# Controller.net
KiCad netlist of a schematic drawn in EAGLE
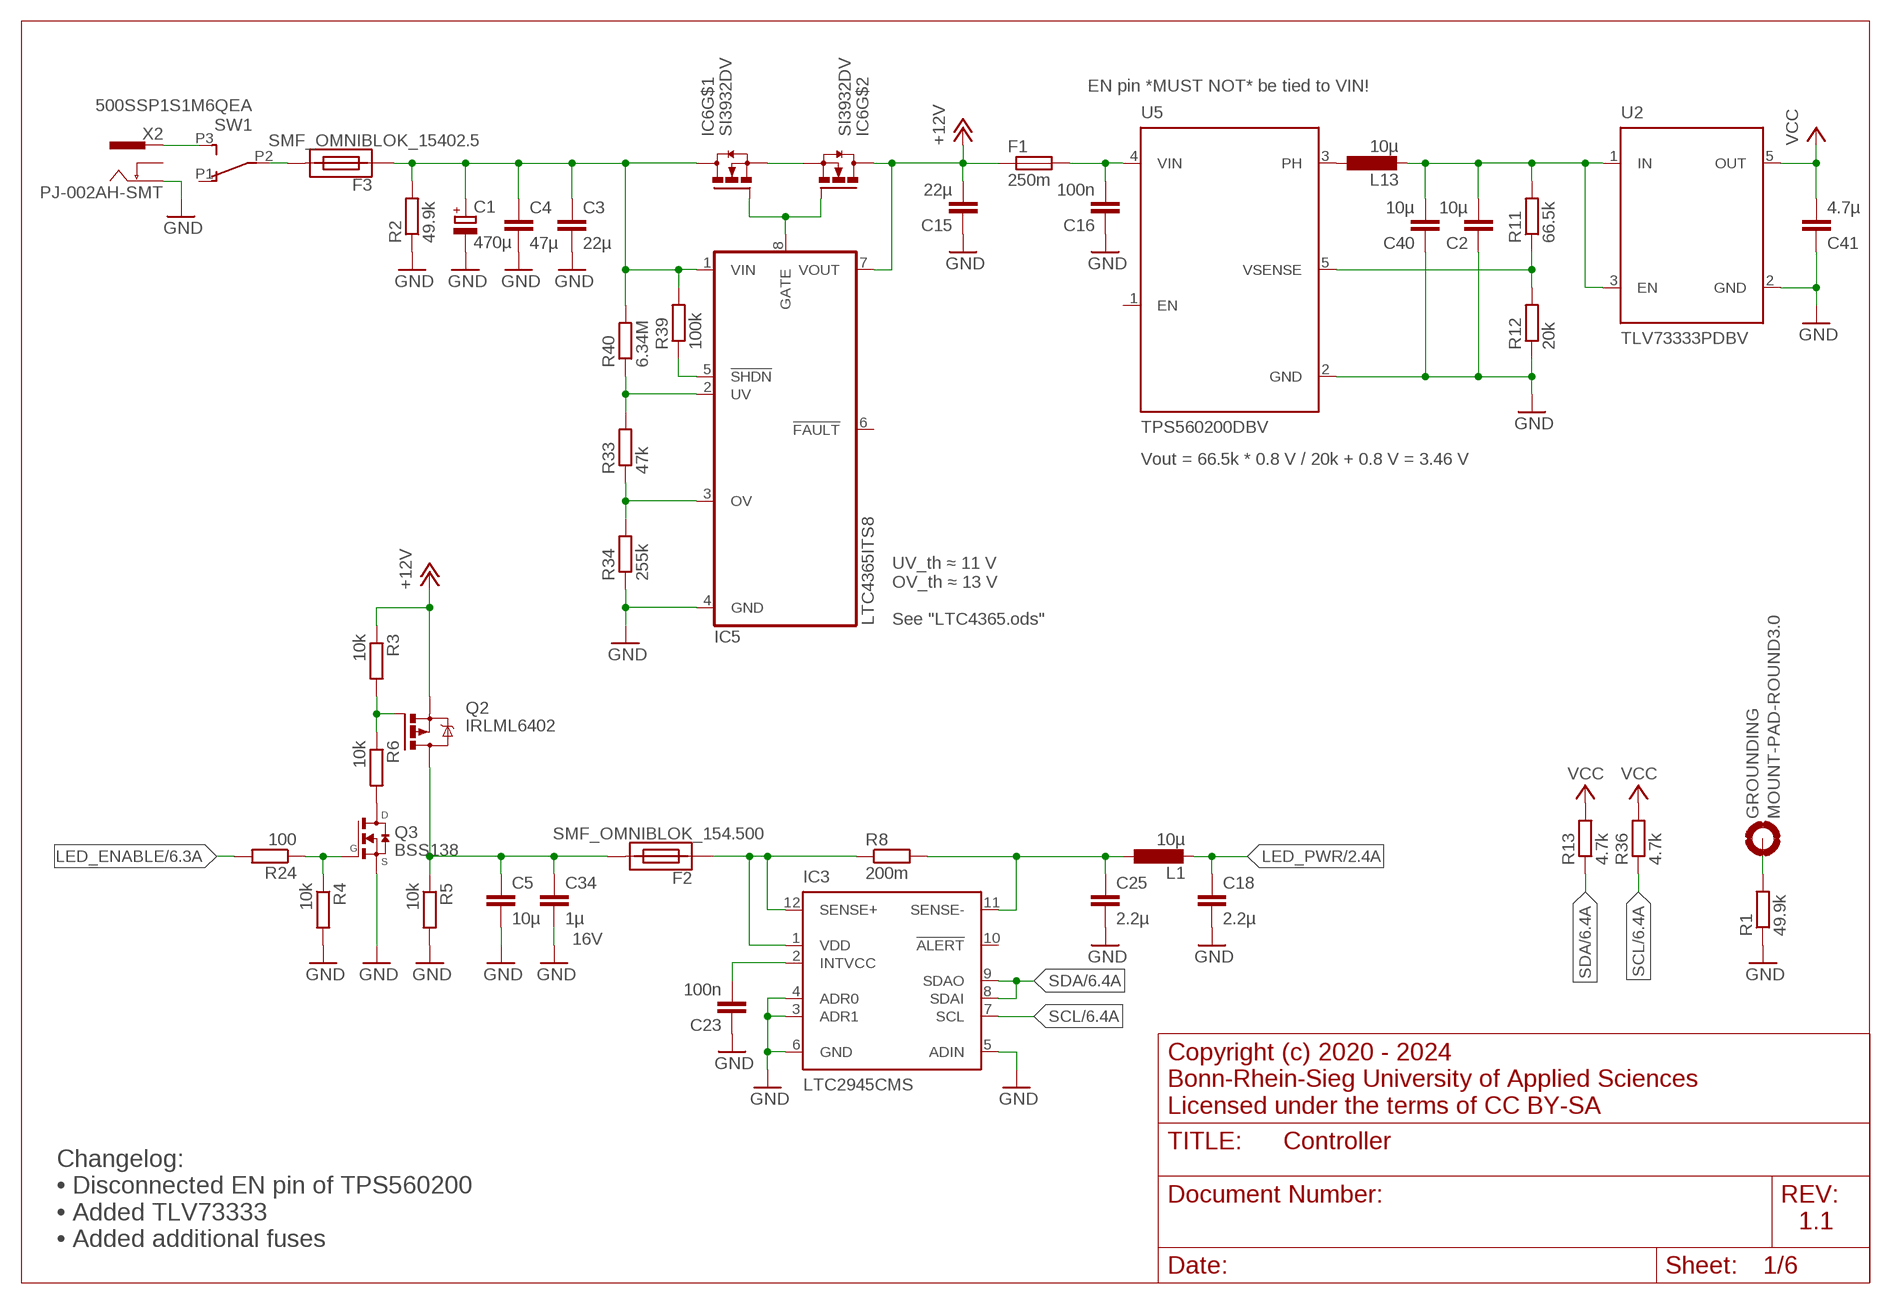
[diagram p0: schematic, sheet 1]
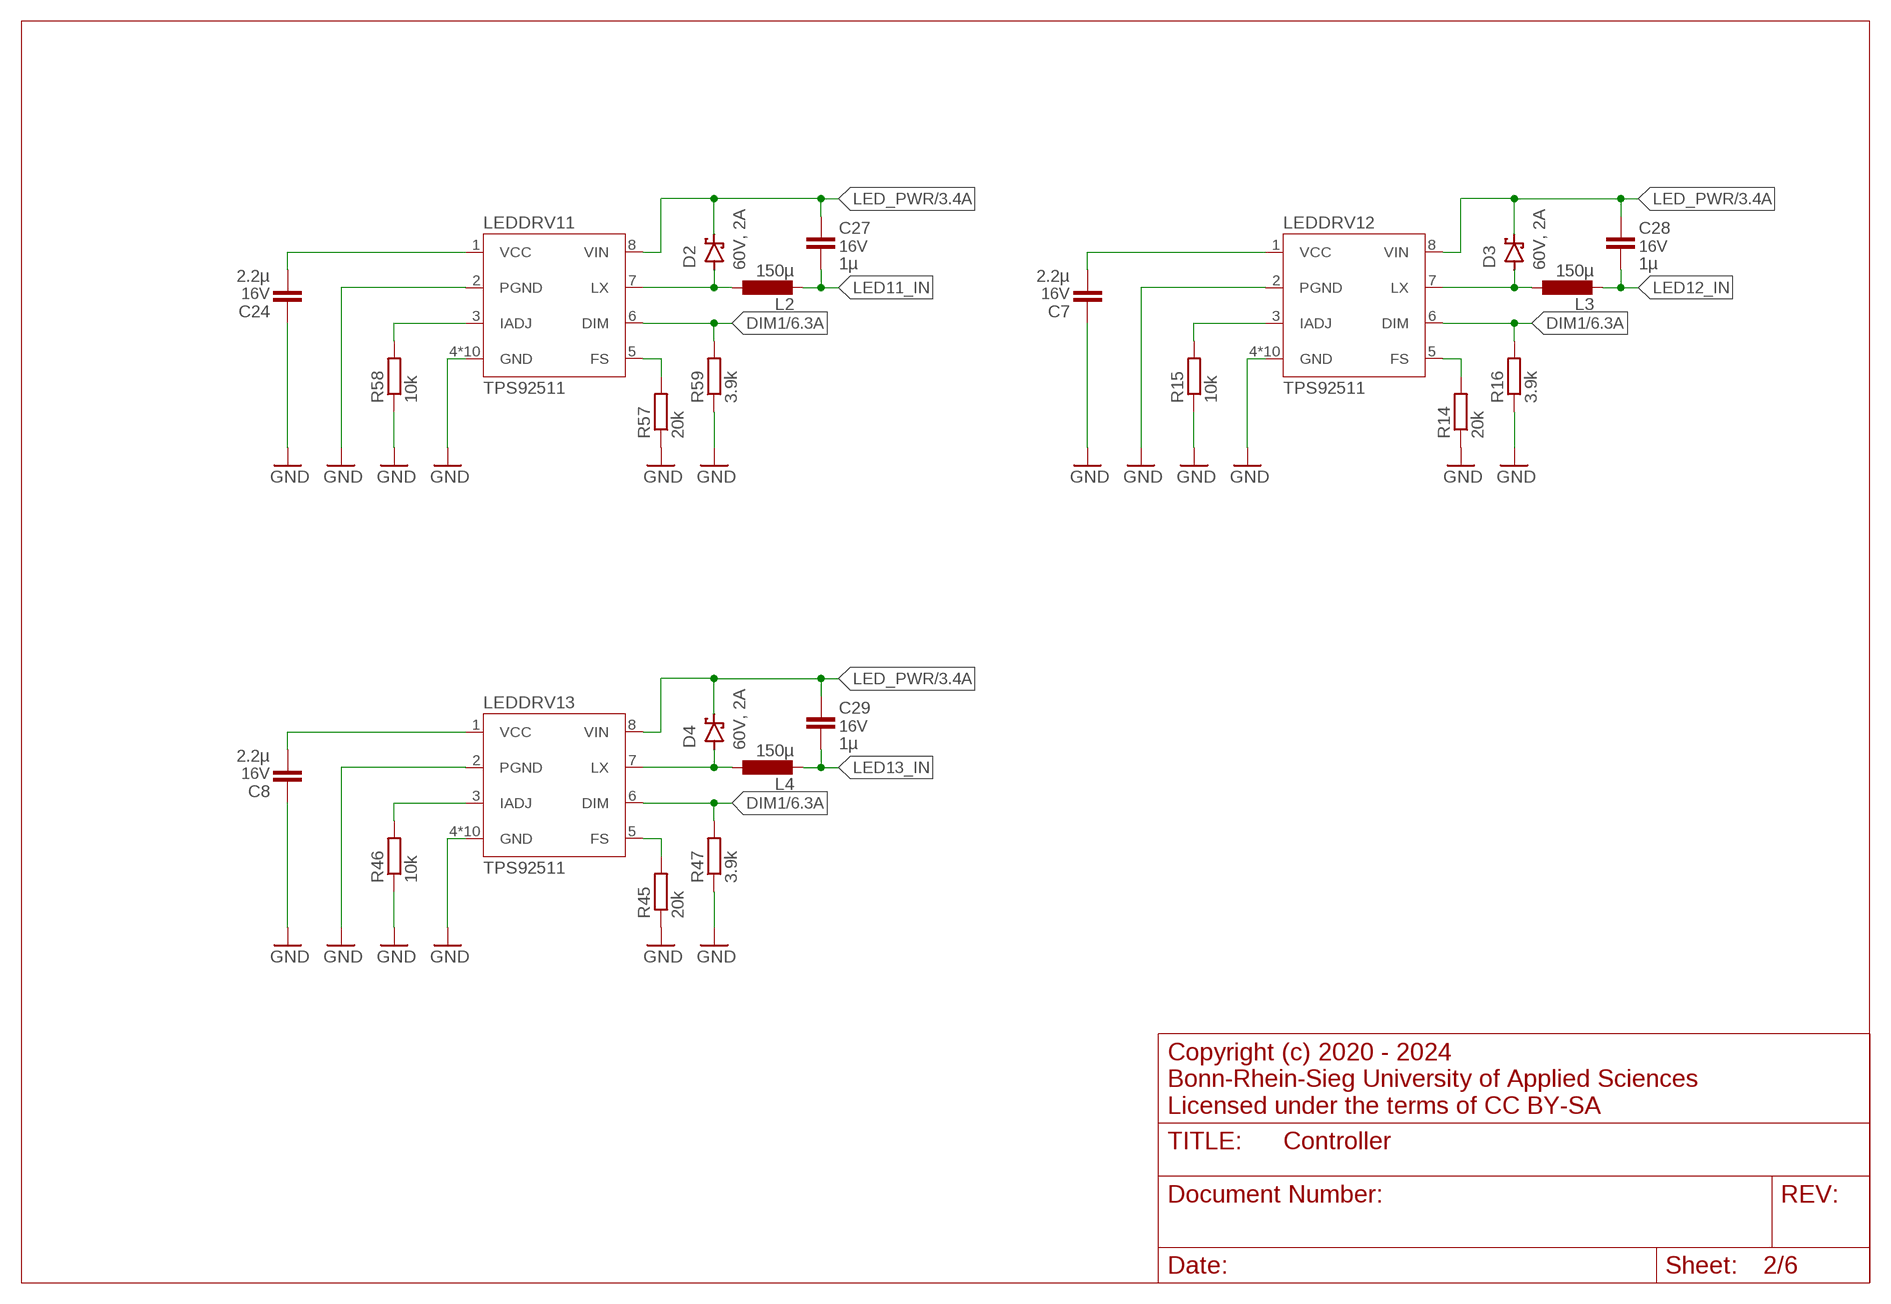
[diagram p1: schematic, sheet 2]
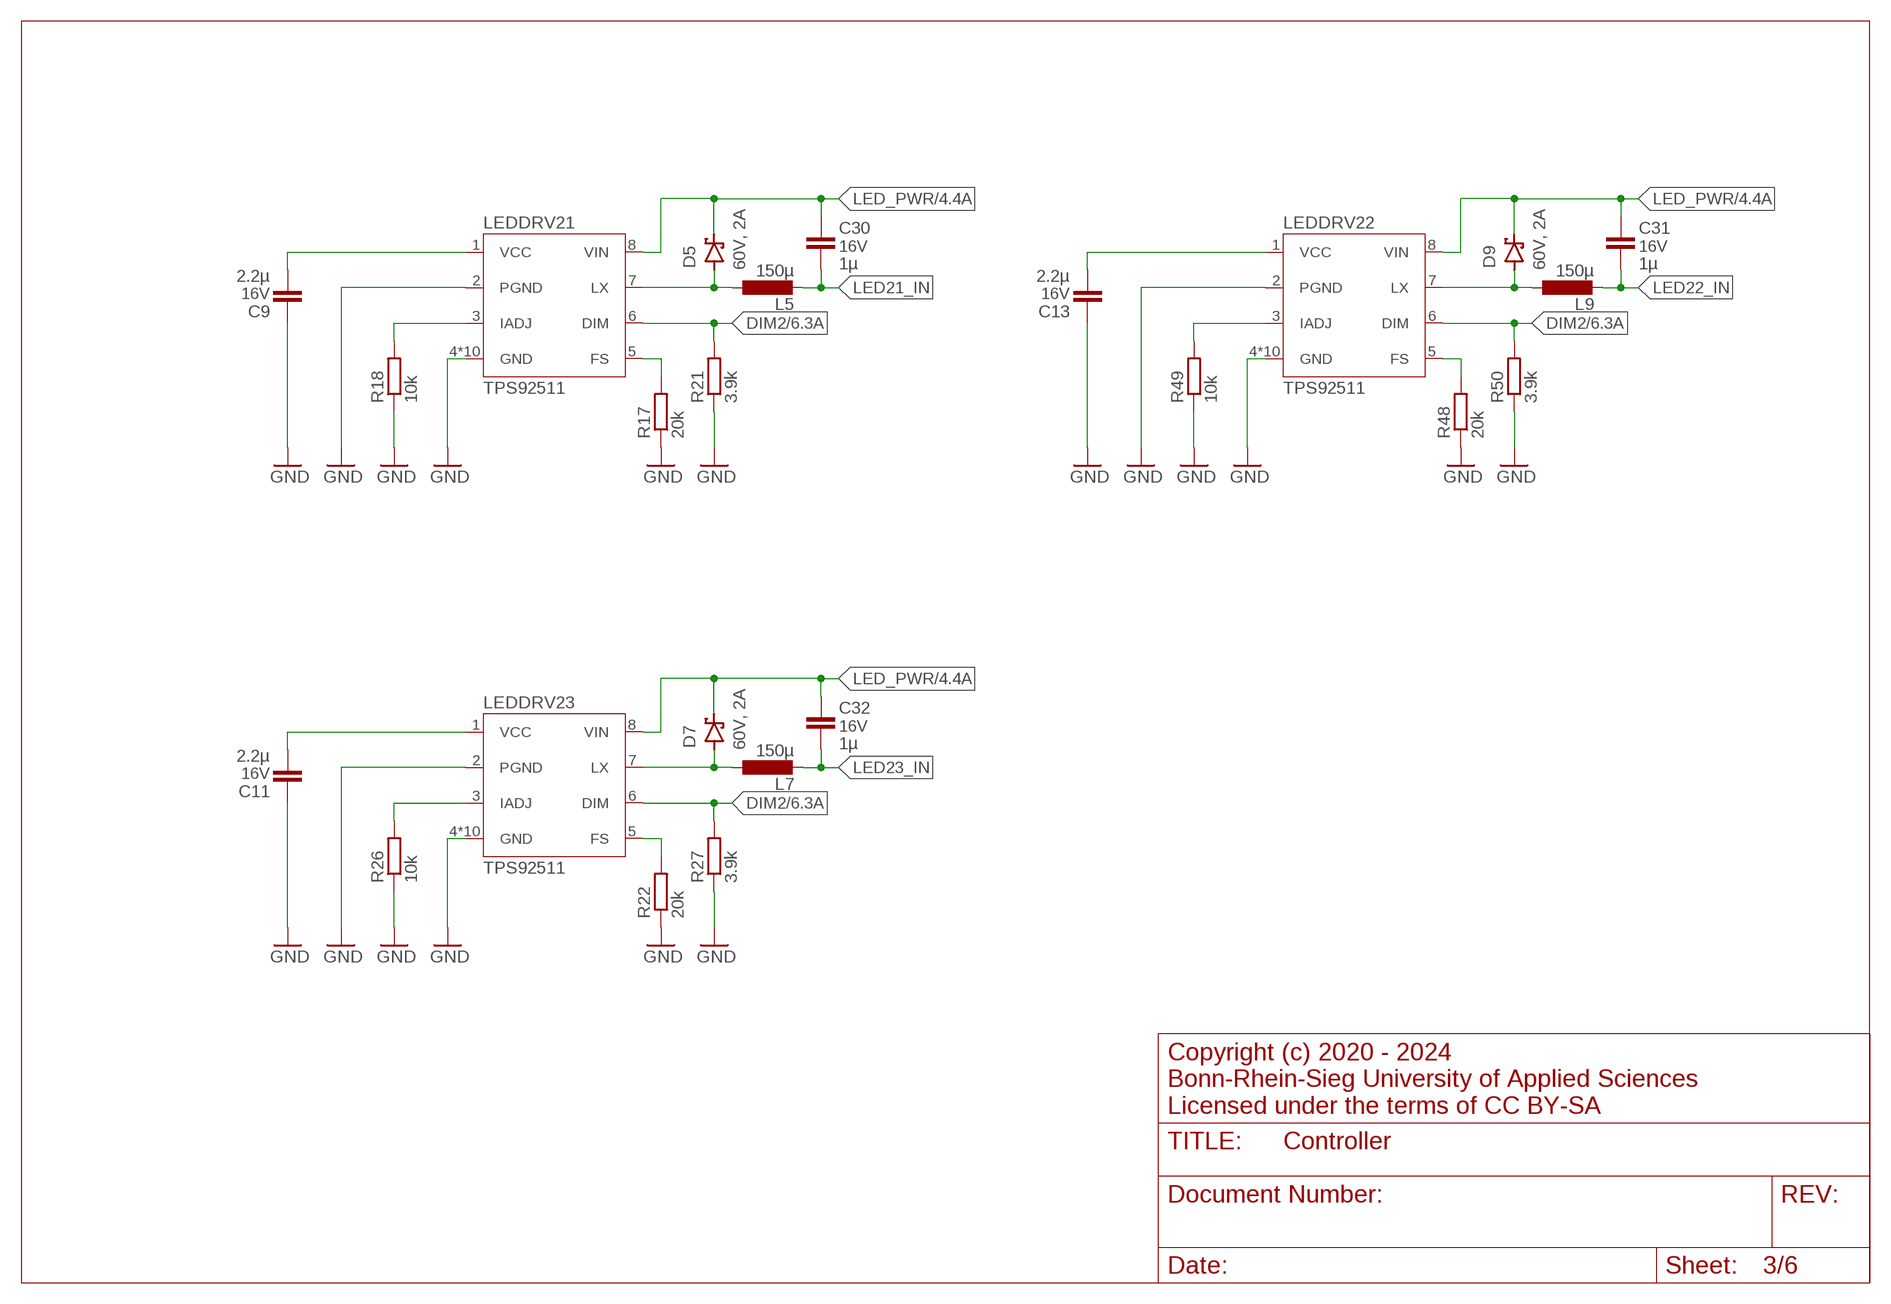
[diagram p2: schematic, sheet 3]
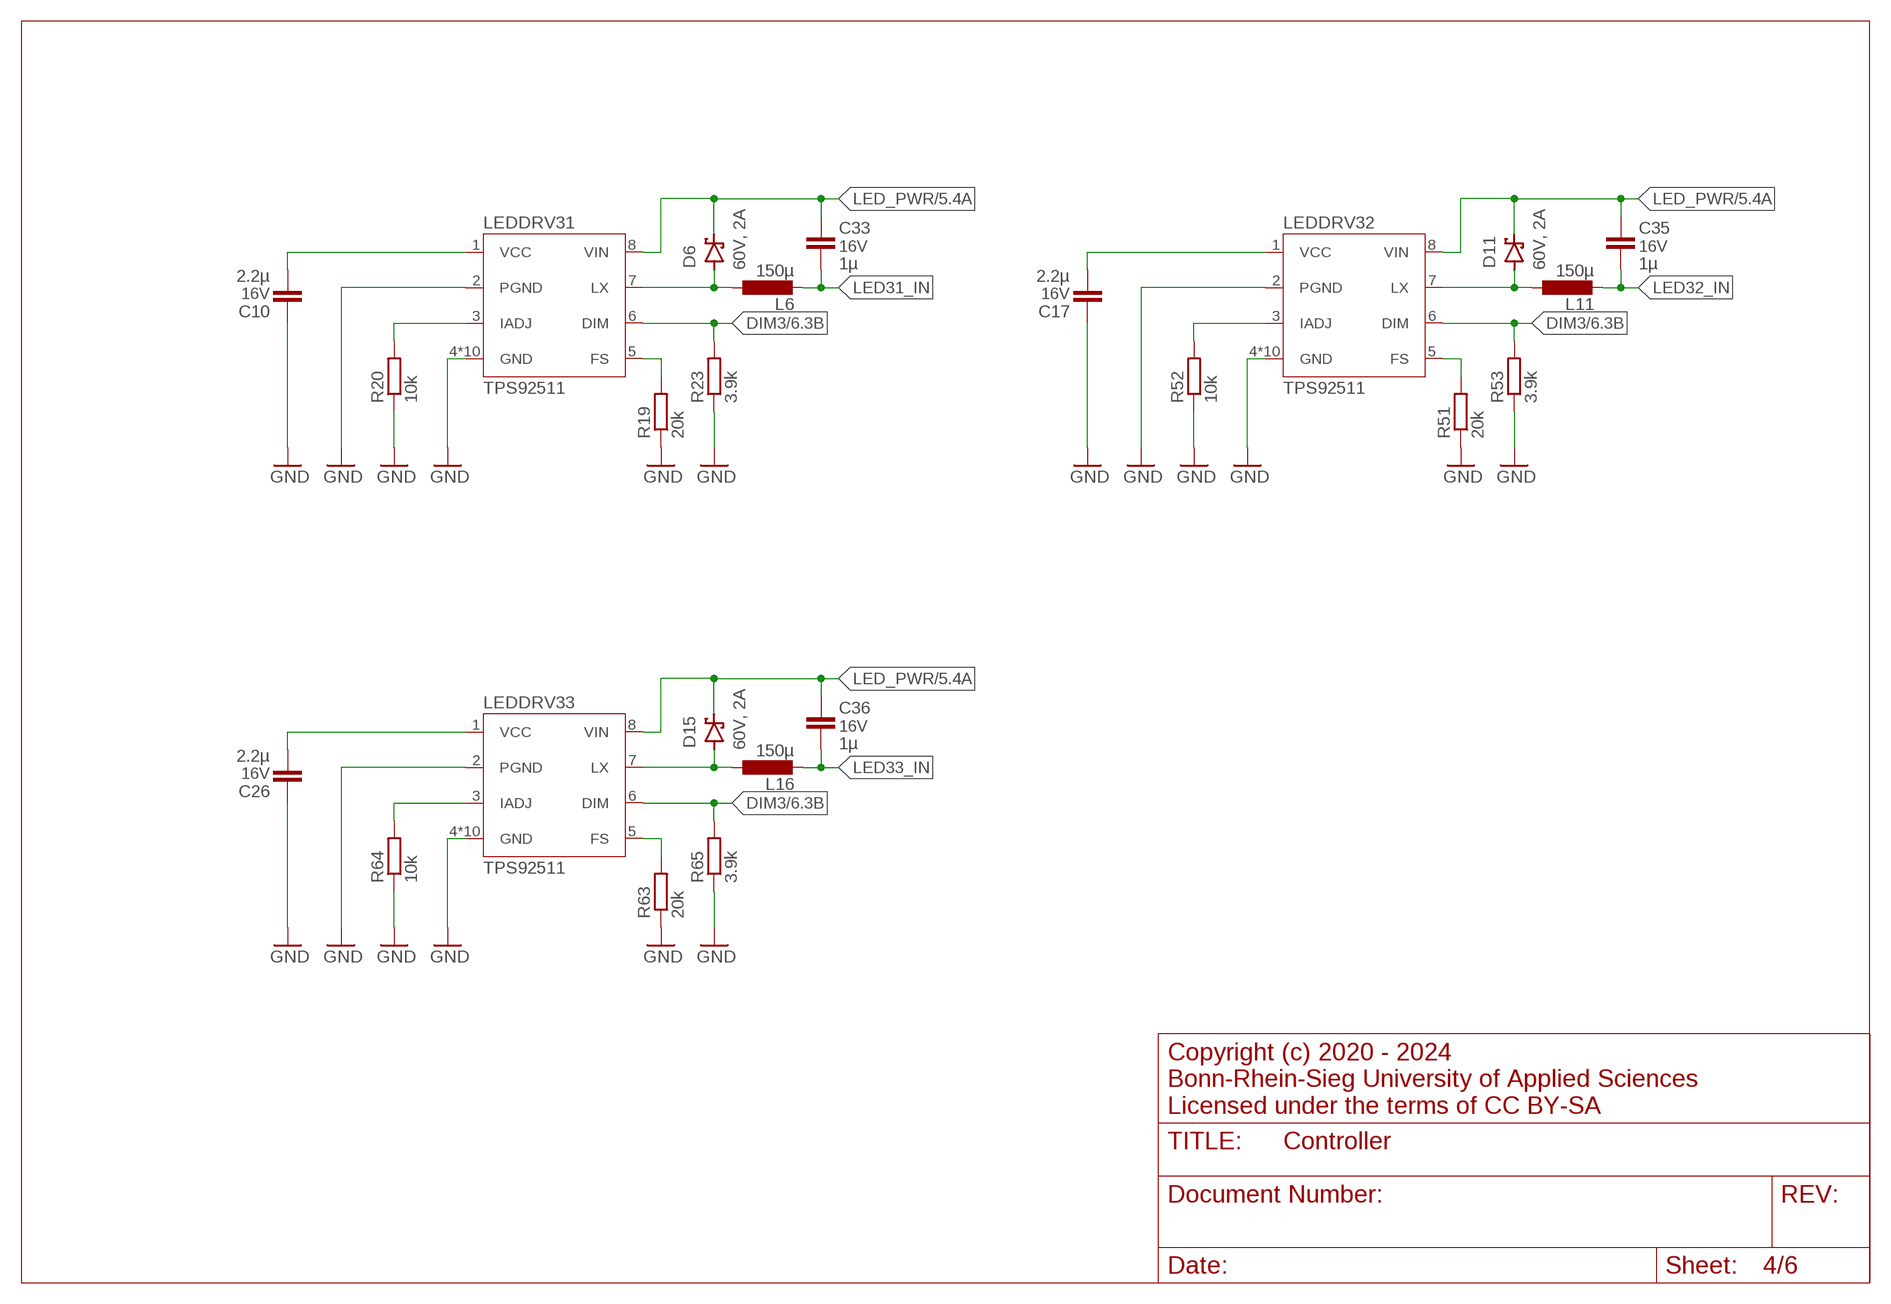
[diagram p3: schematic, sheet 4]
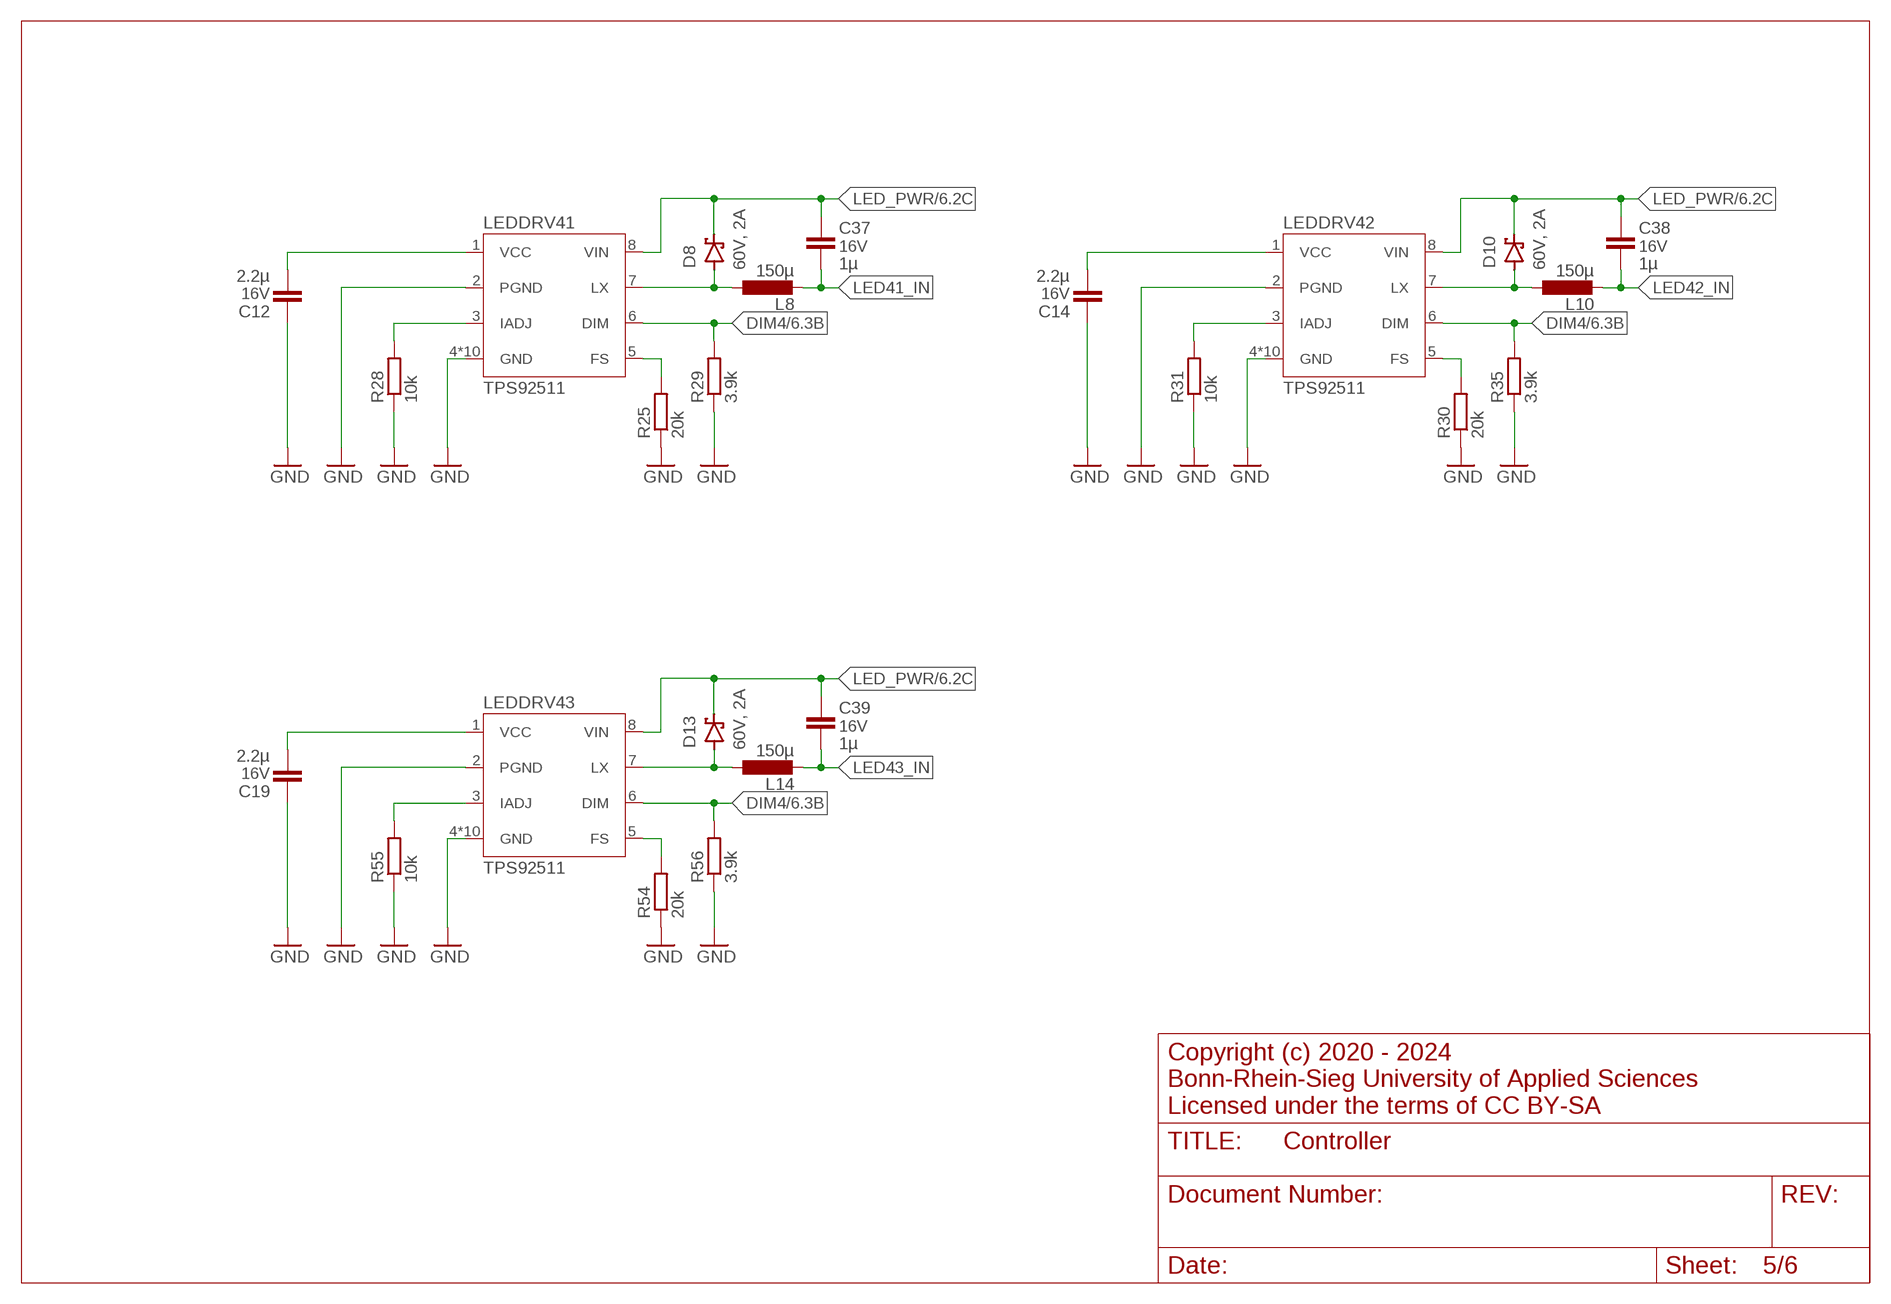
[diagram p4: schematic, sheet 5]
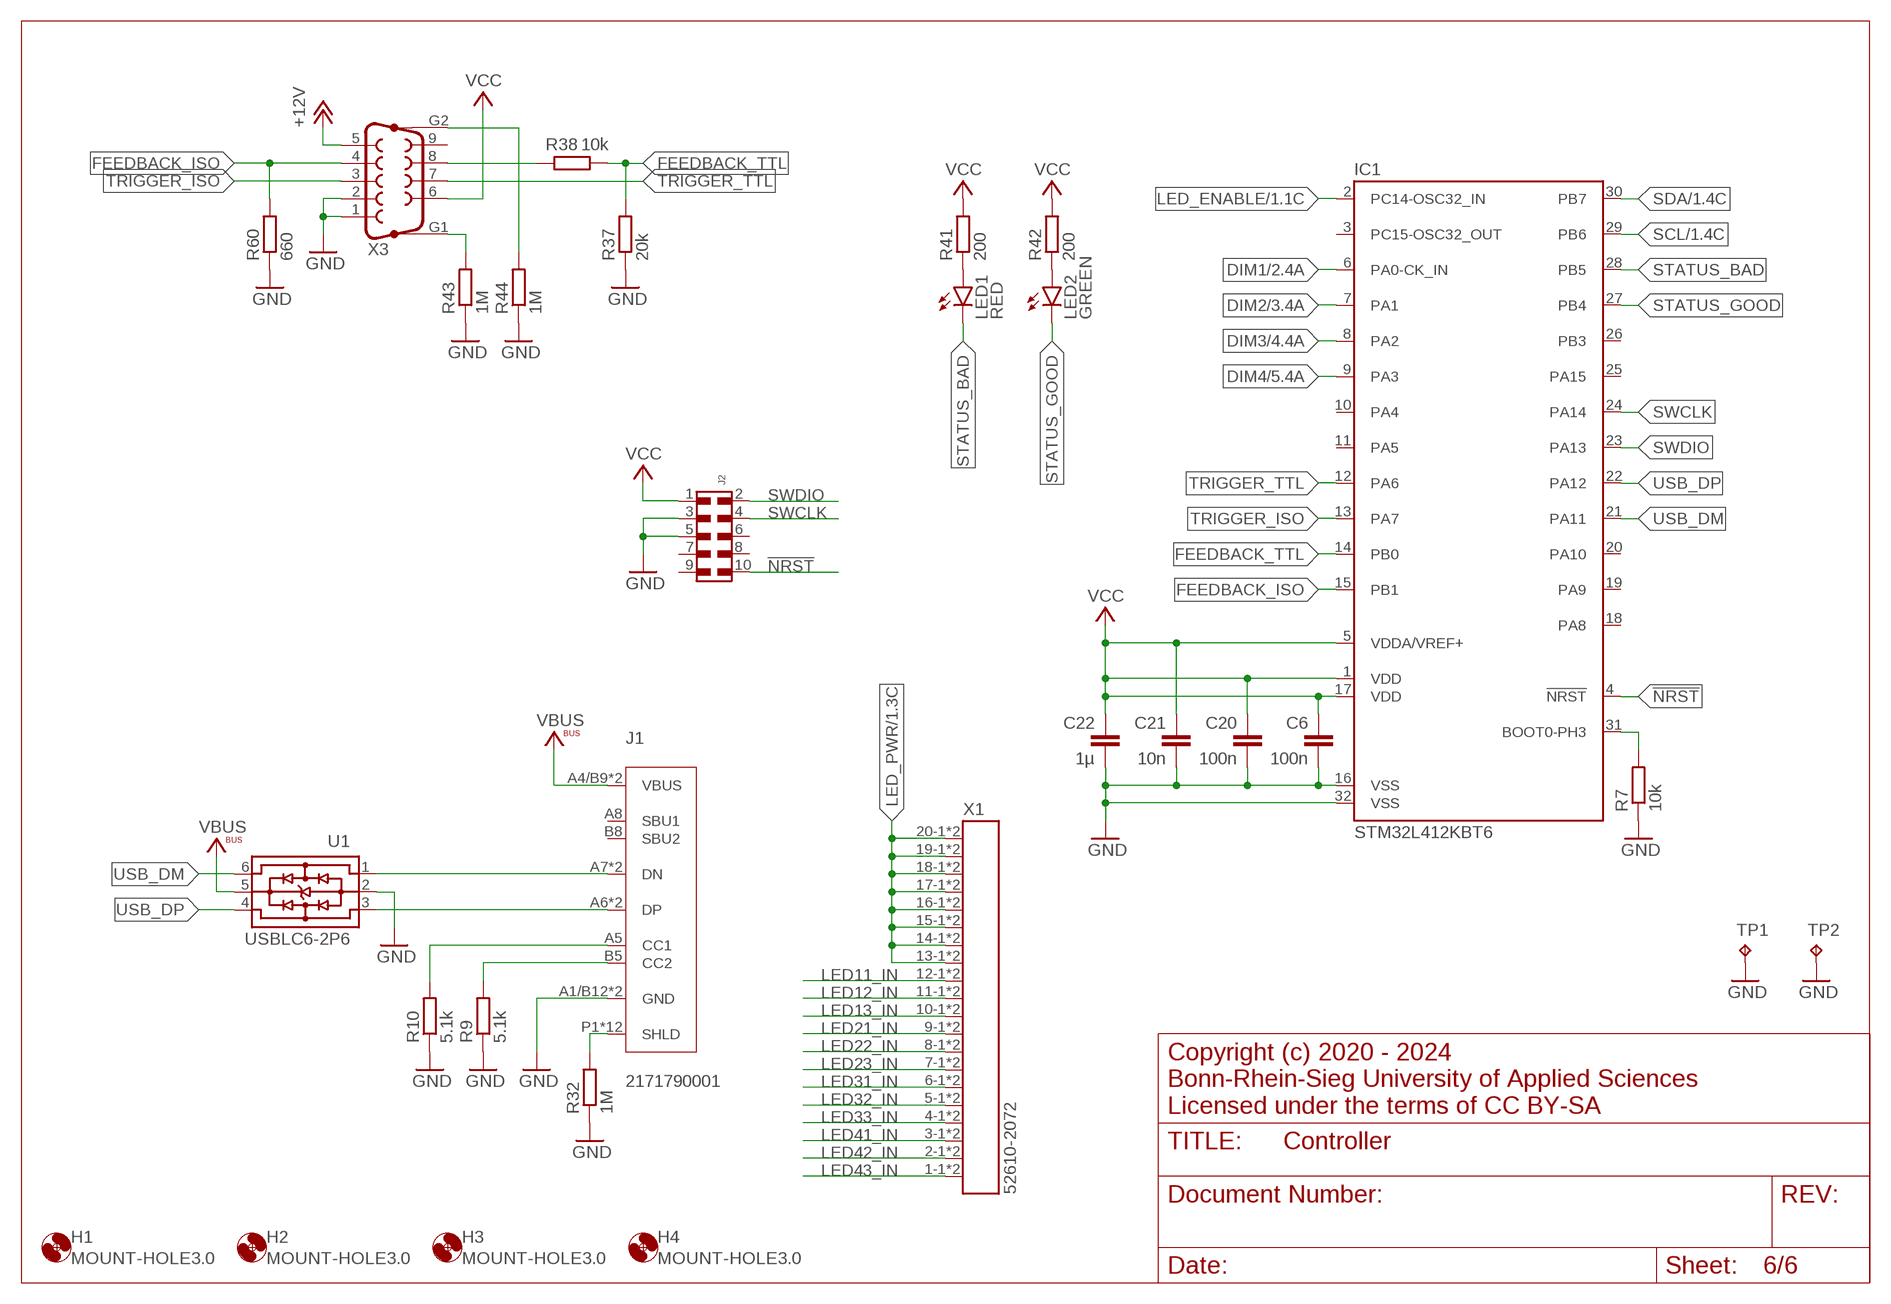
[diagram p5: schematic, sheet 6]

(export (version "E")
  (design (tool "Eeschema 10.0.6"))
  (components
    (comp (ref "C6")
      (value "100n")
      (footprint "eagle-import:C0603")
      (libsource (lib "eagle-import") (part "rcl_334_C-EUC0603"))
    )
    (comp (ref "C20")
      (value "100n")
      (footprint "eagle-import:C0603")
      (libsource (lib "eagle-import") (part "rcl_334_C-EUC0603"))
    )
    (comp (ref "C21")
      (value "10n")
      (footprint "eagle-import:C0603")
      (libsource (lib "eagle-import") (part "rcl_334_C-EUC0603"))
    )
    (comp (ref "C22")
      (value "1µ")
      (footprint "eagle-import:C0603")
      (libsource (lib "eagle-import") (part "rcl_334_C-EUC0603"))
    )
    (comp (ref "H1")
      (value "MOUNT-HOLE3.0")
      (footprint "eagle-import:3,0")
      (libsource (lib "eagle-import") (part "MOUNT-HOLE3.0"))
    )
    (comp (ref "H2")
      (value "MOUNT-HOLE3.0")
      (footprint "eagle-import:3,0")
      (libsource (lib "eagle-import") (part "MOUNT-HOLE3.0"))
    )
    (comp (ref "H3")
      (value "MOUNT-HOLE3.0")
      (footprint "eagle-import:3,0")
      (libsource (lib "eagle-import") (part "MOUNT-HOLE3.0"))
    )
    (comp (ref "H4")
      (value "MOUNT-HOLE3.0")
      (footprint "eagle-import:3,0")
      (libsource (lib "eagle-import") (part "MOUNT-HOLE3.0"))
    )
    (comp (ref "IC1")
      (value "STM32L412KBT6")
      (footprint "eagle-import:LQFP32")
      (libsource (lib "eagle-import") (part "STM32L412K?T6B"))
    )
    (comp (ref "J1")
      (value "2171790001")
      (footprint "eagle-import:2171790001_MOL")
      (fields (field (name "COPYRIGHT") "Copyright (C) 2021 Ultra Librarian. All rights reserved."))
      (libsource (lib "eagle-import") (part "2171790001"))
    )
    (comp (ref "J2")
      (value "6210XX21021_62101021021")
      (footprint "eagle-import:62101021021")
      (libsource (lib "eagle-import") (part "6210XX21021_62101021021"))
    )
    (comp (ref "LED1")
      (value "RED")
      (footprint "eagle-import:LED3MM")
      (libsource (lib "eagle-import") (part "LED3MM"))
    )
    (comp (ref "LED2")
      (value "GREEN")
      (footprint "eagle-import:LED3MM")
      (libsource (lib "eagle-import") (part "LED3MM"))
    )
    (comp (ref "R7")
      (value "10k")
      (footprint "eagle-import:R0603")
      (libsource (lib "eagle-import") (part "rcl_334_R-EU_R0603"))
    )
    (comp (ref "R9")
      (value "5.1k")
      (footprint "eagle-import:R0603")
      (libsource (lib "eagle-import") (part "rcl_334_R-EU_R0603"))
    )
    (comp (ref "R10")
      (value "5.1k")
      (footprint "eagle-import:R0603")
      (libsource (lib "eagle-import") (part "rcl_334_R-EU_R0603"))
    )
    (comp (ref "R32")
      (value "1M")
      (footprint "eagle-import:R0603")
      (libsource (lib "eagle-import") (part "rcl_334_R-EU_R0603"))
    )
    (comp (ref "R37")
      (value "20k")
      (footprint "eagle-import:R0603")
      (libsource (lib "eagle-import") (part "rcl_334_R-EU_R0603"))
    )
    (comp (ref "R38")
      (value "10k")
      (footprint "eagle-import:R0603")
      (libsource (lib "eagle-import") (part "rcl_334_R-EU_R0603"))
    )
    (comp (ref "R41")
      (value "200")
      (footprint "eagle-import:R0603")
      (libsource (lib "eagle-import") (part "rcl_334_R-EU_R0603"))
    )
    (comp (ref "R42")
      (value "200")
      (footprint "eagle-import:R0603")
      (libsource (lib "eagle-import") (part "rcl_334_R-EU_R0603"))
    )
    (comp (ref "R43")
      (value "1M")
      (footprint "eagle-import:R0603")
      (libsource (lib "eagle-import") (part "rcl_334_R-EU_R0603"))
    )
    (comp (ref "R44")
      (value "1M")
      (footprint "eagle-import:R0603")
      (libsource (lib "eagle-import") (part "rcl_334_R-EU_R0603"))
    )
    (comp (ref "R60")
      (value "660")
      (footprint "eagle-import:R0603")
      (libsource (lib "eagle-import") (part "rcl_334_R-EU_R0603"))
    )
    (comp (ref "TP1")
      (value "TP3.8X2.03")
      (footprint "eagle-import:3.8X2.03")
      (libsource (lib "eagle-import") (part "TP3.8X2.03"))
    )
    (comp (ref "TP2")
      (value "TP3.8X2.03")
      (footprint "eagle-import:3.8X2.03")
      (libsource (lib "eagle-import") (part "TP3.8X2.03"))
    )
    (comp (ref "U1")
      (value "USBLC6-2P6")
      (footprint "eagle-import:SOT-666")
      (libsource (lib "eagle-import") (part "USBLC6-2P6"))
    )
    (comp (ref "X1")
      (value "52610-2072")
      (footprint "eagle-import:52610-2072")
      (libsource (lib "eagle-import") (part "52610-2072"))
    )
    (comp (ref "X3")
      (value "F09HP")
      (footprint "eagle-import:F09HP")
      (libsource (lib "eagle-import") (part "F09HP"))
    )
    (comp (ref "C9")
      (value "2.2µ")
      (footprint "eagle-import:C0603")
      (fields (field (name "RATING") "16V"))
      (libsource (lib "eagle-import") (part "rcl_334_C-EUC0603"))
    )
    (comp (ref "C11")
      (value "2.2µ")
      (footprint "eagle-import:C0603")
      (fields (field (name "RATING") "16V"))
      (libsource (lib "eagle-import") (part "rcl_334_C-EUC0603"))
    )
    (comp (ref "C13")
      (value "2.2µ")
      (footprint "eagle-import:C0603")
      (fields (field (name "RATING") "16V"))
      (libsource (lib "eagle-import") (part "rcl_334_C-EUC0603"))
    )
    (comp (ref "C30")
      (value "1µ")
      (footprint "eagle-import:C0805")
      (fields (field (name "RATING") "16V"))
      (libsource (lib "eagle-import") (part "rcl_334_C-EUC0805"))
    )
    (comp (ref "C31")
      (value "1µ")
      (footprint "eagle-import:C0805")
      (fields (field (name "RATING") "16V"))
      (libsource (lib "eagle-import") (part "rcl_334_C-EUC0805"))
    )
    (comp (ref "C32")
      (value "1µ")
      (footprint "eagle-import:C0805")
      (fields (field (name "RATING") "16V"))
      (libsource (lib "eagle-import") (part "rcl_334_C-EUC0805"))
    )
    (comp (ref "D5")
      (value "60V, 2A")
      (footprint "eagle-import:SMB")
      (libsource (lib "eagle-import") (part "SCHOTTKY-DIODESMD"))
    )
    (comp (ref "D7")
      (value "60V, 2A")
      (footprint "eagle-import:SMB")
      (libsource (lib "eagle-import") (part "SCHOTTKY-DIODESMD"))
    )
    (comp (ref "D9")
      (value "60V, 2A")
      (footprint "eagle-import:SMB")
      (libsource (lib "eagle-import") (part "SCHOTTKY-DIODESMD"))
    )
    (comp (ref "L5")
      (value "150µ")
      (footprint "eagle-import:SMD")
      (libsource (lib "eagle-import") (part "LQH44PH151MPR"))
    )
    (comp (ref "L7")
      (value "150µ")
      (footprint "eagle-import:SMD")
      (libsource (lib "eagle-import") (part "LQH44PH151MPR"))
    )
    (comp (ref "L9")
      (value "150µ")
      (footprint "eagle-import:SMD")
      (libsource (lib "eagle-import") (part "LQH44PH151MPR"))
    )
    (comp (ref "LEDDRV21")
      (value "TPS92511")
      (footprint "eagle-import:SOIC-8-EP")
      (libsource (lib "eagle-import") (part "TPS92511"))
    )
    (comp (ref "LEDDRV22")
      (value "TPS92511")
      (footprint "eagle-import:SOIC-8-EP")
      (libsource (lib "eagle-import") (part "TPS92511"))
    )
    (comp (ref "LEDDRV23")
      (value "TPS92511")
      (footprint "eagle-import:SOIC-8-EP")
      (libsource (lib "eagle-import") (part "TPS92511"))
    )
    (comp (ref "R17")
      (value "20k")
      (footprint "eagle-import:R0603")
      (libsource (lib "eagle-import") (part "rcl_334_R-EU_R0603"))
    )
    (comp (ref "R18")
      (value "10k")
      (footprint "eagle-import:R0603")
      (libsource (lib "eagle-import") (part "rcl_334_R-EU_R0603"))
    )
    (comp (ref "R21")
      (value "3.9k")
      (footprint "eagle-import:R0603")
      (libsource (lib "eagle-import") (part "rcl_334_R-EU_R0603"))
    )
    (comp (ref "R22")
      (value "20k")
      (footprint "eagle-import:R0603")
      (libsource (lib "eagle-import") (part "rcl_334_R-EU_R0603"))
    )
    (comp (ref "R26")
      (value "10k")
      (footprint "eagle-import:R0603")
      (libsource (lib "eagle-import") (part "rcl_334_R-EU_R0603"))
    )
    (comp (ref "R27")
      (value "3.9k")
      (footprint "eagle-import:R0603")
      (libsource (lib "eagle-import") (part "rcl_334_R-EU_R0603"))
    )
    (comp (ref "R48")
      (value "20k")
      (footprint "eagle-import:R0603")
      (libsource (lib "eagle-import") (part "rcl_334_R-EU_R0603"))
    )
    (comp (ref "R49")
      (value "10k")
      (footprint "eagle-import:R0603")
      (libsource (lib "eagle-import") (part "rcl_334_R-EU_R0603"))
    )
    (comp (ref "R50")
      (value "3.9k")
      (footprint "eagle-import:R0603")
      (libsource (lib "eagle-import") (part "rcl_334_R-EU_R0603"))
    )
    (comp (ref "C1")
      (value "470µ")
      (footprint "eagle-import:UD-10X10_NICHICON")
      (libsource (lib "eagle-import") (part "CPOL-EUUD-10X10"))
    )
    (comp (ref "C2")
      (value "10µ")
      (footprint "eagle-import:C0805")
      (libsource (lib "eagle-import") (part "C-EUC0805"))
    )
    (comp (ref "C3")
      (value "22µ")
      (footprint "eagle-import:C1206")
      (libsource (lib "eagle-import") (part "rcl_334_C-EUC1206"))
    )
    (comp (ref "C4")
      (value "47µ")
      (footprint "eagle-import:C1206")
      (libsource (lib "eagle-import") (part "rcl_334_C-EUC1206"))
    )
    (comp (ref "C5")
      (value "10µ")
      (footprint "eagle-import:C0805")
      (libsource (lib "eagle-import") (part "C-EUC0805"))
    )
    (comp (ref "C15")
      (value "22µ")
      (footprint "eagle-import:C0805")
      (libsource (lib "eagle-import") (part "C-EUC0805"))
    )
    (comp (ref "C16")
      (value "100n")
      (footprint "eagle-import:C0603")
      (libsource (lib "eagle-import") (part "C-EUC0603"))
    )
    (comp (ref "C18")
      (value "2.2µ")
      (footprint "eagle-import:C0805")
      (libsource (lib "eagle-import") (part "C-EUC0805"))
    )
    (comp (ref "C23")
      (value "100n")
      (footprint "eagle-import:C0603")
      (libsource (lib "eagle-import") (part "C-EUC0603"))
    )
    (comp (ref "C25")
      (value "2.2µ")
      (footprint "eagle-import:C0805")
      (libsource (lib "eagle-import") (part "C-EUC0805"))
    )
    (comp (ref "C34")
      (value "1µ")
      (footprint "eagle-import:C0805")
      (fields (field (name "RATING") "16V"))
      (libsource (lib "eagle-import") (part "C-EUC0805"))
    )
    (comp (ref "C40")
      (value "10µ")
      (footprint "eagle-import:C0805")
      (libsource (lib "eagle-import") (part "C-EUC0805"))
    )
    (comp (ref "C41")
      (value "4.7µ")
      (footprint "eagle-import:C0805")
      (libsource (lib "eagle-import") (part "C-EUC0805"))
    )
    (comp (ref "F1")
      (value "250m")
      (footprint "eagle-import:R0603")
      (libsource (lib "eagle-import") (part "FUSE0603"))
    )
    (comp (ref "F2")
      (value "SMF_OMNIBLOK_154.500")
      (footprint "eagle-import:NANO2_SMF_FUSEBLOCK")
      (libsource (lib "eagle-import") (part "SMF_OMNIBLOK_154.500"))
    )
    (comp (ref "F3")
      (value "SMF_OMNIBLOK_15402.5")
      (footprint "eagle-import:NANO2_SMF_FUSEBLOCK")
      (libsource (lib "eagle-import") (part "SMF_OMNIBLOK_15402.5"))
    )
    (comp (ref "GROUNDING")
      (value "MOUNT-PAD-ROUND3.0")
      (footprint "eagle-import:3,0-PAD")
      (libsource (lib "eagle-import") (part "MOUNT-PAD-ROUND3.0"))
    )
    (comp (ref "IC3")
      (value "LTC2945CMS")
      (footprint "eagle-import:MSOP12")
      (libsource (lib "eagle-import") (part "LTC2945MSC"))
    )
    (comp (ref "IC5")
      (value "LTC4365ITS8")
      (footprint "eagle-import:TSOT-23-8")
      (libsource (lib "eagle-import") (part "LTC4365TS8I"))
    )
    (comp (ref "IC6")
      (value "SI3932DV")
      (footprint "eagle-import:TSOT-23-6")
      (libsource (lib "eagle-import") (part "SI3932DV"))
    )
    (comp (ref "L1")
      (value "10µ")
      (footprint "eagle-import:SMD")
      (libsource (lib "eagle-import") (part "LQH44PH100MPR"))
    )
    (comp (ref "L13")
      (value "10µ")
      (footprint "eagle-import:2SMD")
      (libsource (lib "eagle-import") (part "VLS3012E?-T100M"))
    )
    (comp (ref "Q2")
      (value "IRLML6402")
      (footprint "eagle-import:MICRO3")
      (libsource (lib "eagle-import") (part "IRLML6402"))
    )
    (comp (ref "Q3")
      (value "BSS138")
      (footprint "eagle-import:SOT23")
      (libsource (lib "eagle-import") (part "BSS138"))
    )
    (comp (ref "R1")
      (value "49.9k")
      (footprint "eagle-import:R0805")
      (libsource (lib "eagle-import") (part "rcl_334_R-EU_R0805"))
    )
    (comp (ref "R2")
      (value "49.9k")
      (footprint "eagle-import:R1206")
      (libsource (lib "eagle-import") (part "rcl_334_R-EU_R1206"))
    )
    (comp (ref "R3")
      (value "10k")
      (footprint "eagle-import:R0603")
      (libsource (lib "eagle-import") (part "R-EU_R0603"))
    )
    (comp (ref "R4")
      (value "10k")
      (footprint "eagle-import:R0603")
      (libsource (lib "eagle-import") (part "R-EU_R0603"))
    )
    (comp (ref "R5")
      (value "10k")
      (footprint "eagle-import:R1206")
      (libsource (lib "eagle-import") (part "R-EU_R1206"))
    )
    (comp (ref "R6")
      (value "10k")
      (footprint "eagle-import:R0603")
      (libsource (lib "eagle-import") (part "R-EU_R0603"))
    )
    (comp (ref "R8")
      (value "200m")
      (footprint "eagle-import:R2512")
      (libsource (lib "eagle-import") (part "rcl_334_R-EU_R2512"))
    )
    (comp (ref "R11")
      (value "66.5k")
      (footprint "eagle-import:R0603")
      (libsource (lib "eagle-import") (part "R-EU_R0603"))
    )
    (comp (ref "R12")
      (value "20k")
      (footprint "eagle-import:R0603")
      (libsource (lib "eagle-import") (part "R-EU_R0603"))
    )
    (comp (ref "R13")
      (value "4.7k")
      (footprint "eagle-import:R0603")
      (libsource (lib "eagle-import") (part "rcl_334_R-EU_R0603"))
    )
    (comp (ref "R24")
      (value "100")
      (footprint "eagle-import:R0603")
      (libsource (lib "eagle-import") (part "R-EU_R0603"))
    )
    (comp (ref "R33")
      (value "47k")
      (footprint "eagle-import:R0603")
      (libsource (lib "eagle-import") (part "R-EU_R0603"))
    )
    (comp (ref "R34")
      (value "255k")
      (footprint "eagle-import:R0603")
      (libsource (lib "eagle-import") (part "R-EU_R0603"))
    )
    (comp (ref "R36")
      (value "4.7k")
      (footprint "eagle-import:R0603")
      (libsource (lib "eagle-import") (part "rcl_334_R-EU_R0603"))
    )
    (comp (ref "R39")
      (value "100k")
      (footprint "eagle-import:R0603")
      (libsource (lib "eagle-import") (part "R-EU_R0603"))
    )
    (comp (ref "R40")
      (value "6.34M")
      (footprint "eagle-import:R0603")
      (libsource (lib "eagle-import") (part "R-EU_R0603"))
    )
    (comp (ref "SW1")
      (value "500SSP1S1M6QEA")
      (footprint "eagle-import:500SSP1S1M6QEA")
      (libsource (lib "eagle-import") (part "500SSP1S1M6QEA"))
    )
    (comp (ref "U2")
      (value "TLV73333PDBV")
      (footprint "eagle-import:SOT-23")
      (libsource (lib "eagle-import") (part "TLV733P?DBV33"))
    )
    (comp (ref "U5")
      (value "TPS560200DBV")
      (footprint "eagle-import:SOT-23")
      (libsource (lib "eagle-import") (part "TPS560200DBV"))
    )
    (comp (ref "X2")
      (value "PJ-002AH-SMT")
      (footprint "eagle-import:PJ-002AH-SMT")
      (libsource (lib "eagle-import") (part "PJ-002AH-SMT"))
    )
    (comp (ref "C12")
      (value "2.2µ")
      (footprint "eagle-import:C0603")
      (fields (field (name "RATING") "16V"))
      (libsource (lib "eagle-import") (part "rcl_334_C-EUC0603"))
    )
    (comp (ref "C14")
      (value "2.2µ")
      (footprint "eagle-import:C0603")
      (fields (field (name "RATING") "16V"))
      (libsource (lib "eagle-import") (part "rcl_334_C-EUC0603"))
    )
    (comp (ref "C19")
      (value "2.2µ")
      (footprint "eagle-import:C0603")
      (fields (field (name "RATING") "16V"))
      (libsource (lib "eagle-import") (part "rcl_334_C-EUC0603"))
    )
    (comp (ref "C37")
      (value "1µ")
      (footprint "eagle-import:C0805")
      (fields (field (name "RATING") "16V"))
      (libsource (lib "eagle-import") (part "rcl_334_C-EUC0805"))
    )
    (comp (ref "C38")
      (value "1µ")
      (footprint "eagle-import:C0805")
      (fields (field (name "RATING") "16V"))
      (libsource (lib "eagle-import") (part "rcl_334_C-EUC0805"))
    )
    (comp (ref "C39")
      (value "1µ")
      (footprint "eagle-import:C0805")
      (fields (field (name "RATING") "16V"))
      (libsource (lib "eagle-import") (part "rcl_334_C-EUC0805"))
    )
    (comp (ref "D8")
      (value "60V, 2A")
      (footprint "eagle-import:SMB")
      (libsource (lib "eagle-import") (part "SCHOTTKY-DIODESMD"))
    )
    (comp (ref "D10")
      (value "60V, 2A")
      (footprint "eagle-import:SMB")
      (libsource (lib "eagle-import") (part "SCHOTTKY-DIODESMD"))
    )
    (comp (ref "D13")
      (value "60V, 2A")
      (footprint "eagle-import:SMB")
      (libsource (lib "eagle-import") (part "SCHOTTKY-DIODESMD"))
    )
    (comp (ref "L8")
      (value "150µ")
      (footprint "eagle-import:SMD")
      (libsource (lib "eagle-import") (part "LQH44PH151MPR"))
    )
    (comp (ref "L10")
      (value "150µ")
      (footprint "eagle-import:SMD")
      (libsource (lib "eagle-import") (part "LQH44PH151MPR"))
    )
    (comp (ref "L14")
      (value "150µ")
      (footprint "eagle-import:SMD")
      (libsource (lib "eagle-import") (part "LQH44PH151MPR"))
    )
    (comp (ref "LEDDRV41")
      (value "TPS92511")
      (footprint "eagle-import:SOIC-8-EP")
      (libsource (lib "eagle-import") (part "TPS92511"))
    )
    (comp (ref "LEDDRV42")
      (value "TPS92511")
      (footprint "eagle-import:SOIC-8-EP")
      (libsource (lib "eagle-import") (part "TPS92511"))
    )
    (comp (ref "LEDDRV43")
      (value "TPS92511")
      (footprint "eagle-import:SOIC-8-EP")
      (libsource (lib "eagle-import") (part "TPS92511"))
    )
    (comp (ref "R25")
      (value "20k")
      (footprint "eagle-import:R0603")
      (libsource (lib "eagle-import") (part "rcl_334_R-EU_R0603"))
    )
    (comp (ref "R28")
      (value "10k")
      (footprint "eagle-import:R0603")
      (libsource (lib "eagle-import") (part "rcl_334_R-EU_R0603"))
    )
    (comp (ref "R29")
      (value "3.9k")
      (footprint "eagle-import:R0603")
      (libsource (lib "eagle-import") (part "rcl_334_R-EU_R0603"))
    )
    (comp (ref "R30")
      (value "20k")
      (footprint "eagle-import:R0603")
      (libsource (lib "eagle-import") (part "rcl_334_R-EU_R0603"))
    )
    (comp (ref "R31")
      (value "10k")
      (footprint "eagle-import:R0603")
      (libsource (lib "eagle-import") (part "rcl_334_R-EU_R0603"))
    )
    (comp (ref "R35")
      (value "3.9k")
      (footprint "eagle-import:R0603")
      (libsource (lib "eagle-import") (part "rcl_334_R-EU_R0603"))
    )
    (comp (ref "R54")
      (value "20k")
      (footprint "eagle-import:R0603")
      (libsource (lib "eagle-import") (part "rcl_334_R-EU_R0603"))
    )
    (comp (ref "R55")
      (value "10k")
      (footprint "eagle-import:R0603")
      (libsource (lib "eagle-import") (part "rcl_334_R-EU_R0603"))
    )
    (comp (ref "R56")
      (value "3.9k")
      (footprint "eagle-import:R0603")
      (libsource (lib "eagle-import") (part "rcl_334_R-EU_R0603"))
    )
    (comp (ref "C10")
      (value "2.2µ")
      (footprint "eagle-import:C0603")
      (fields (field (name "RATING") "16V"))
      (libsource (lib "eagle-import") (part "rcl_334_C-EUC0603"))
    )
    (comp (ref "C17")
      (value "2.2µ")
      (footprint "eagle-import:C0603")
      (fields (field (name "RATING") "16V"))
      (libsource (lib "eagle-import") (part "rcl_334_C-EUC0603"))
    )
    (comp (ref "C26")
      (value "2.2µ")
      (footprint "eagle-import:C0603")
      (fields (field (name "RATING") "16V"))
      (libsource (lib "eagle-import") (part "rcl_334_C-EUC0603"))
    )
    (comp (ref "C33")
      (value "1µ")
      (footprint "eagle-import:C0805")
      (fields (field (name "RATING") "16V"))
      (libsource (lib "eagle-import") (part "rcl_334_C-EUC0805"))
    )
    (comp (ref "C35")
      (value "1µ")
      (footprint "eagle-import:C0805")
      (fields (field (name "RATING") "16V"))
      (libsource (lib "eagle-import") (part "rcl_334_C-EUC0805"))
    )
    (comp (ref "C36")
      (value "1µ")
      (footprint "eagle-import:C0805")
      (fields (field (name "RATING") "16V"))
      (libsource (lib "eagle-import") (part "rcl_334_C-EUC0805"))
    )
    (comp (ref "D6")
      (value "60V, 2A")
      (footprint "eagle-import:SMB")
      (libsource (lib "eagle-import") (part "SCHOTTKY-DIODESMD"))
    )
    (comp (ref "D11")
      (value "60V, 2A")
      (footprint "eagle-import:SMB")
      (libsource (lib "eagle-import") (part "SCHOTTKY-DIODESMD"))
    )
    (comp (ref "D15")
      (value "60V, 2A")
      (footprint "eagle-import:SMB")
      (libsource (lib "eagle-import") (part "SCHOTTKY-DIODESMD"))
    )
    (comp (ref "L6")
      (value "150µ")
      (footprint "eagle-import:SMD")
      (libsource (lib "eagle-import") (part "LQH44PH151MPR"))
    )
    (comp (ref "L11")
      (value "150µ")
      (footprint "eagle-import:SMD")
      (libsource (lib "eagle-import") (part "LQH44PH151MPR"))
    )
    (comp (ref "L16")
      (value "150µ")
      (footprint "eagle-import:SMD")
      (libsource (lib "eagle-import") (part "LQH44PH151MPR"))
    )
    (comp (ref "LEDDRV31")
      (value "TPS92511")
      (footprint "eagle-import:SOIC-8-EP")
      (libsource (lib "eagle-import") (part "TPS92511"))
    )
    (comp (ref "LEDDRV32")
      (value "TPS92511")
      (footprint "eagle-import:SOIC-8-EP")
      (libsource (lib "eagle-import") (part "TPS92511"))
    )
    (comp (ref "LEDDRV33")
      (value "TPS92511")
      (footprint "eagle-import:SOIC-8-EP")
      (libsource (lib "eagle-import") (part "TPS92511"))
    )
    (comp (ref "R19")
      (value "20k")
      (footprint "eagle-import:R0603")
      (libsource (lib "eagle-import") (part "rcl_334_R-EU_R0603"))
    )
    (comp (ref "R20")
      (value "10k")
      (footprint "eagle-import:R0603")
      (libsource (lib "eagle-import") (part "rcl_334_R-EU_R0603"))
    )
    (comp (ref "R23")
      (value "3.9k")
      (footprint "eagle-import:R0603")
      (libsource (lib "eagle-import") (part "rcl_334_R-EU_R0603"))
    )
    (comp (ref "R51")
      (value "20k")
      (footprint "eagle-import:R0603")
      (libsource (lib "eagle-import") (part "rcl_334_R-EU_R0603"))
    )
    (comp (ref "R52")
      (value "10k")
      (footprint "eagle-import:R0603")
      (libsource (lib "eagle-import") (part "rcl_334_R-EU_R0603"))
    )
    (comp (ref "R53")
      (value "3.9k")
      (footprint "eagle-import:R0603")
      (libsource (lib "eagle-import") (part "rcl_334_R-EU_R0603"))
    )
    (comp (ref "R63")
      (value "20k")
      (footprint "eagle-import:R0603")
      (libsource (lib "eagle-import") (part "rcl_334_R-EU_R0603"))
    )
    (comp (ref "R64")
      (value "10k")
      (footprint "eagle-import:R0603")
      (libsource (lib "eagle-import") (part "rcl_334_R-EU_R0603"))
    )
    (comp (ref "R65")
      (value "3.9k")
      (footprint "eagle-import:R0603")
      (libsource (lib "eagle-import") (part "rcl_334_R-EU_R0603"))
    )
    (comp (ref "C7")
      (value "2.2µ")
      (footprint "eagle-import:C0603")
      (fields (field (name "RATING") "16V"))
      (libsource (lib "eagle-import") (part "rcl_334_C-EUC0603"))
    )
    (comp (ref "C8")
      (value "2.2µ")
      (footprint "eagle-import:C0603")
      (fields (field (name "RATING") "16V"))
      (libsource (lib "eagle-import") (part "rcl_334_C-EUC0603"))
    )
    (comp (ref "C24")
      (value "2.2µ")
      (footprint "eagle-import:C0603")
      (fields (field (name "RATING") "16V"))
      (libsource (lib "eagle-import") (part "rcl_334_C-EUC0603"))
    )
    (comp (ref "C27")
      (value "1µ")
      (footprint "eagle-import:C0805")
      (fields (field (name "RATING") "16V"))
      (libsource (lib "eagle-import") (part "rcl_334_C-EUC0805"))
    )
    (comp (ref "C28")
      (value "1µ")
      (footprint "eagle-import:C0805")
      (fields (field (name "RATING") "16V"))
      (libsource (lib "eagle-import") (part "rcl_334_C-EUC0805"))
    )
    (comp (ref "C29")
      (value "1µ")
      (footprint "eagle-import:C0805")
      (fields (field (name "RATING") "16V"))
      (libsource (lib "eagle-import") (part "rcl_334_C-EUC0805"))
    )
    (comp (ref "D2")
      (value "60V, 2A")
      (footprint "eagle-import:SMB")
      (libsource (lib "eagle-import") (part "SCHOTTKY-DIODESMD"))
    )
    (comp (ref "D3")
      (value "60V, 2A")
      (footprint "eagle-import:SMB")
      (libsource (lib "eagle-import") (part "SCHOTTKY-DIODESMD"))
    )
    (comp (ref "D4")
      (value "60V, 2A")
      (footprint "eagle-import:SMB")
      (libsource (lib "eagle-import") (part "SCHOTTKY-DIODESMD"))
    )
    (comp (ref "L2")
      (value "150µ")
      (footprint "eagle-import:SMD")
      (libsource (lib "eagle-import") (part "LQH44PH151MPR"))
    )
    (comp (ref "L3")
      (value "150µ")
      (footprint "eagle-import:SMD")
      (libsource (lib "eagle-import") (part "LQH44PH151MPR"))
    )
    (comp (ref "L4")
      (value "150µ")
      (footprint "eagle-import:SMD")
      (libsource (lib "eagle-import") (part "LQH44PH151MPR"))
    )
    (comp (ref "LEDDRV11")
      (value "TPS92511")
      (footprint "eagle-import:SOIC-8-EP")
      (libsource (lib "eagle-import") (part "TPS92511"))
    )
    (comp (ref "LEDDRV12")
      (value "TPS92511")
      (footprint "eagle-import:SOIC-8-EP")
      (libsource (lib "eagle-import") (part "TPS92511"))
    )
    (comp (ref "LEDDRV13")
      (value "TPS92511")
      (footprint "eagle-import:SOIC-8-EP")
      (libsource (lib "eagle-import") (part "TPS92511"))
    )
    (comp (ref "R14")
      (value "20k")
      (footprint "eagle-import:R0603")
      (libsource (lib "eagle-import") (part "rcl_334_R-EU_R0603"))
    )
    (comp (ref "R15")
      (value "10k")
      (footprint "eagle-import:R0603")
      (libsource (lib "eagle-import") (part "rcl_334_R-EU_R0603"))
    )
    (comp (ref "R16")
      (value "3.9k")
      (footprint "eagle-import:R0603")
      (libsource (lib "eagle-import") (part "rcl_334_R-EU_R0603"))
    )
    (comp (ref "R45")
      (value "20k")
      (footprint "eagle-import:R0603")
      (libsource (lib "eagle-import") (part "rcl_334_R-EU_R0603"))
    )
    (comp (ref "R46")
      (value "10k")
      (footprint "eagle-import:R0603")
      (libsource (lib "eagle-import") (part "rcl_334_R-EU_R0603"))
    )
    (comp (ref "R47")
      (value "3.9k")
      (footprint "eagle-import:R0603")
      (libsource (lib "eagle-import") (part "rcl_334_R-EU_R0603"))
    )
    (comp (ref "R57")
      (value "20k")
      (footprint "eagle-import:R0603")
      (libsource (lib "eagle-import") (part "rcl_334_R-EU_R0603"))
    )
    (comp (ref "R58")
      (value "10k")
      (footprint "eagle-import:R0603")
      (libsource (lib "eagle-import") (part "rcl_334_R-EU_R0603"))
    )
    (comp (ref "R59")
      (value "3.9k")
      (footprint "eagle-import:R0603")
      (libsource (lib "eagle-import") (part "rcl_334_R-EU_R0603"))
    )
  )
  (nets
    (net (code "1") (name "+12V") (class "Default")
      (node (ref "C15") (pin "2") (pinfunction "2_2") (pintype "passive"))
      (node (ref "F1") (pin "1") (pinfunction "1_1") (pintype "passive"))
      (node (ref "IC5") (pin "7") (pinfunction "VOUT_7") (pintype "passive"))
      (node (ref "IC6") (pin "4") (pinfunction "D_4") (pintype "passive"))
      (node (ref "Q2") (pin "2") (pinfunction "S_2") (pintype "passive"))
      (node (ref "R3") (pin "1") (pinfunction "1_1") (pintype "passive"))
      (node (ref "X3") (pin "5") (pinfunction "5_5") (pintype "passive"))
    )
    (net (code "2") (name "DIM1") (class "Default")
      (node (ref "IC1") (pin "6") (pinfunction "PA0-CK_IN_6") (pintype "bidirectional"))
      (node (ref "LEDDRV11") (pin "6") (pinfunction "DIM_6") (pintype "passive"))
      (node (ref "LEDDRV12") (pin "6") (pinfunction "DIM_6") (pintype "passive"))
      (node (ref "LEDDRV13") (pin "6") (pinfunction "DIM_6") (pintype "passive"))
      (node (ref "R16") (pin "2") (pinfunction "2_2") (pintype "passive"))
      (node (ref "R47") (pin "2") (pinfunction "2_2") (pintype "passive"))
      (node (ref "R59") (pin "2") (pinfunction "2_2") (pintype "passive"))
    )
    (net (code "3") (name "DIM2") (class "Default")
      (node (ref "IC1") (pin "7") (pinfunction "PA1_7") (pintype "bidirectional"))
      (node (ref "LEDDRV21") (pin "6") (pinfunction "DIM_6") (pintype "passive"))
      (node (ref "LEDDRV22") (pin "6") (pinfunction "DIM_6") (pintype "passive"))
      (node (ref "LEDDRV23") (pin "6") (pinfunction "DIM_6") (pintype "passive"))
      (node (ref "R21") (pin "2") (pinfunction "2_2") (pintype "passive"))
      (node (ref "R27") (pin "2") (pinfunction "2_2") (pintype "passive"))
      (node (ref "R50") (pin "2") (pinfunction "2_2") (pintype "passive"))
    )
    (net (code "4") (name "DIM3") (class "Default")
      (node (ref "IC1") (pin "8") (pinfunction "PA2_8") (pintype "bidirectional"))
      (node (ref "LEDDRV31") (pin "6") (pinfunction "DIM_6") (pintype "passive"))
      (node (ref "LEDDRV32") (pin "6") (pinfunction "DIM_6") (pintype "passive"))
      (node (ref "LEDDRV33") (pin "6") (pinfunction "DIM_6") (pintype "passive"))
      (node (ref "R23") (pin "2") (pinfunction "2_2") (pintype "passive"))
      (node (ref "R53") (pin "2") (pinfunction "2_2") (pintype "passive"))
      (node (ref "R65") (pin "2") (pinfunction "2_2") (pintype "passive"))
    )
    (net (code "5") (name "DIM4") (class "Default")
      (node (ref "IC1") (pin "9") (pinfunction "PA3_9") (pintype "bidirectional"))
      (node (ref "LEDDRV41") (pin "6") (pinfunction "DIM_6") (pintype "passive"))
      (node (ref "LEDDRV42") (pin "6") (pinfunction "DIM_6") (pintype "passive"))
      (node (ref "LEDDRV43") (pin "6") (pinfunction "DIM_6") (pintype "passive"))
      (node (ref "R29") (pin "2") (pinfunction "2_2") (pintype "passive"))
      (node (ref "R35") (pin "2") (pinfunction "2_2") (pintype "passive"))
      (node (ref "R56") (pin "2") (pinfunction "2_2") (pintype "passive"))
    )
    (net (code "6") (name "FEEDBACK_ISO") (class "Default")
      (node (ref "IC1") (pin "15") (pinfunction "PB1_15") (pintype "bidirectional"))
      (node (ref "R60") (pin "2") (pinfunction "2_2") (pintype "passive"))
      (node (ref "X3") (pin "4") (pinfunction "4_4") (pintype "passive"))
    )
    (net (code "7") (name "FEEDBACK_TTL") (class "Default")
      (node (ref "IC1") (pin "14") (pinfunction "PB0_14") (pintype "bidirectional"))
      (node (ref "R37") (pin "2") (pinfunction "2_2") (pintype "passive"))
      (node (ref "R38") (pin "1") (pinfunction "1_1") (pintype "passive"))
    )
    (net (code "8") (name "GND") (class "Default")
      (node (ref "C1") (pin "-") (pinfunction "-_-") (pintype "passive"))
      (node (ref "C10") (pin "1") (pinfunction "1_1") (pintype "passive"))
      (node (ref "C11") (pin "1") (pinfunction "1_1") (pintype "passive"))
      (node (ref "C12") (pin "1") (pinfunction "1_1") (pintype "passive"))
      (node (ref "C13") (pin "1") (pinfunction "1_1") (pintype "passive"))
      (node (ref "C14") (pin "1") (pinfunction "1_1") (pintype "passive"))
      (node (ref "C15") (pin "1") (pinfunction "1_1") (pintype "passive"))
      (node (ref "C16") (pin "1") (pinfunction "1_1") (pintype "passive"))
      (node (ref "C17") (pin "1") (pinfunction "1_1") (pintype "passive"))
      (node (ref "C18") (pin "2") (pinfunction "2_2") (pintype "passive"))
      (node (ref "C19") (pin "1") (pinfunction "1_1") (pintype "passive"))
      (node (ref "C2") (pin "1") (pinfunction "1_1") (pintype "passive"))
      (node (ref "C20") (pin "2") (pinfunction "2_2") (pintype "passive"))
      (node (ref "C21") (pin "2") (pinfunction "2_2") (pintype "passive"))
      (node (ref "C22") (pin "2") (pinfunction "2_2") (pintype "passive"))
      (node (ref "C23") (pin "1") (pinfunction "1_1") (pintype "passive"))
      (node (ref "C24") (pin "1") (pinfunction "1_1") (pintype "passive"))
      (node (ref "C25") (pin "2") (pinfunction "2_2") (pintype "passive"))
      (node (ref "C26") (pin "1") (pinfunction "1_1") (pintype "passive"))
      (node (ref "C3") (pin "2") (pinfunction "2_2") (pintype "passive"))
      (node (ref "C34") (pin "2") (pinfunction "2_2") (pintype "passive"))
      (node (ref "C4") (pin "2") (pinfunction "2_2") (pintype "passive"))
      (node (ref "C40") (pin "1") (pinfunction "1_1") (pintype "passive"))
      (node (ref "C41") (pin "1") (pinfunction "1_1") (pintype "passive"))
      (node (ref "C5") (pin "2") (pinfunction "2_2") (pintype "passive"))
      (node (ref "C6") (pin "2") (pinfunction "2_2") (pintype "passive"))
      (node (ref "C7") (pin "1") (pinfunction "1_1") (pintype "passive"))
      (node (ref "C8") (pin "1") (pinfunction "1_1") (pintype "passive"))
      (node (ref "C9") (pin "1") (pinfunction "1_1") (pintype "passive"))
      (node (ref "IC1") (pin "16") (pinfunction "VSS_16") (pintype "bidirectional"))
      (node (ref "IC1") (pin "32") (pinfunction "VSS_32") (pintype "bidirectional"))
      (node (ref "IC3") (pin "3") (pinfunction "ADR1_3") (pintype "passive"))
      (node (ref "IC3") (pin "4") (pinfunction "ADR0_4") (pintype "passive"))
      (node (ref "IC3") (pin "5") (pinfunction "ADIN_5") (pintype "input"))
      (node (ref "IC3") (pin "6") (pinfunction "GND_6") (pintype "power_in"))
      (node (ref "IC5") (pin "4") (pinfunction "GND_4") (pintype "passive"))
      (node (ref "J1") (pin "A1/B12") (pinfunction "GND_A1/B12") (pintype "passive"))
      (node (ref "J1") (pin "B1/A12") (pinfunction "GND_B1/A12") (pintype "passive"))
      (node (ref "J2") (pin "3") (pinfunction "3_3") (pintype "passive"))
      (node (ref "J2") (pin "5") (pinfunction "5_5") (pintype "passive"))
      (node (ref "LEDDRV11") (pin "2") (pinfunction "PGND_2") (pintype "passive"))
      (node (ref "LEDDRV11") (pin "4") (pinfunction "GND_4") (pintype "power_in"))
      (node (ref "LEDDRV11") (pin "EPAD") (pinfunction "GND_EPAD") (pintype "power_in"))
      (node (ref "LEDDRV11") (pin "P$1") (pinfunction "GND_P$1") (pintype "power_in"))
      (node (ref "LEDDRV11") (pin "P$2") (pinfunction "GND_P$2") (pintype "power_in"))
      (node (ref "LEDDRV11") (pin "P$3") (pinfunction "GND_P$3") (pintype "power_in"))
      (node (ref "LEDDRV11") (pin "P$4") (pinfunction "GND_P$4") (pintype "power_in"))
      (node (ref "LEDDRV11") (pin "P$5") (pinfunction "GND_P$5") (pintype "power_in"))
      (node (ref "LEDDRV11") (pin "P$6") (pinfunction "GND_P$6") (pintype "power_in"))
      (node (ref "LEDDRV11") (pin "P$7") (pinfunction "GND_P$7") (pintype "power_in"))
      (node (ref "LEDDRV11") (pin "P$8") (pinfunction "GND_P$8") (pintype "power_in"))
      (node (ref "LEDDRV12") (pin "2") (pinfunction "PGND_2") (pintype "passive"))
      (node (ref "LEDDRV12") (pin "4") (pinfunction "GND_4") (pintype "power_in"))
      (node (ref "LEDDRV12") (pin "EPAD") (pinfunction "GND_EPAD") (pintype "power_in"))
      (node (ref "LEDDRV12") (pin "P$1") (pinfunction "GND_P$1") (pintype "power_in"))
      (node (ref "LEDDRV12") (pin "P$2") (pinfunction "GND_P$2") (pintype "power_in"))
      (node (ref "LEDDRV12") (pin "P$3") (pinfunction "GND_P$3") (pintype "power_in"))
      (node (ref "LEDDRV12") (pin "P$4") (pinfunction "GND_P$4") (pintype "power_in"))
      (node (ref "LEDDRV12") (pin "P$5") (pinfunction "GND_P$5") (pintype "power_in"))
      (node (ref "LEDDRV12") (pin "P$6") (pinfunction "GND_P$6") (pintype "power_in"))
      (node (ref "LEDDRV12") (pin "P$7") (pinfunction "GND_P$7") (pintype "power_in"))
      (node (ref "LEDDRV12") (pin "P$8") (pinfunction "GND_P$8") (pintype "power_in"))
      (node (ref "LEDDRV13") (pin "2") (pinfunction "PGND_2") (pintype "passive"))
      (node (ref "LEDDRV13") (pin "4") (pinfunction "GND_4") (pintype "power_in"))
      (node (ref "LEDDRV13") (pin "EPAD") (pinfunction "GND_EPAD") (pintype "power_in"))
      (node (ref "LEDDRV13") (pin "P$1") (pinfunction "GND_P$1") (pintype "power_in"))
      (node (ref "LEDDRV13") (pin "P$2") (pinfunction "GND_P$2") (pintype "power_in"))
      (node (ref "LEDDRV13") (pin "P$3") (pinfunction "GND_P$3") (pintype "power_in"))
      (node (ref "LEDDRV13") (pin "P$4") (pinfunction "GND_P$4") (pintype "power_in"))
      (node (ref "LEDDRV13") (pin "P$5") (pinfunction "GND_P$5") (pintype "power_in"))
      (node (ref "LEDDRV13") (pin "P$6") (pinfunction "GND_P$6") (pintype "power_in"))
      (node (ref "LEDDRV13") (pin "P$7") (pinfunction "GND_P$7") (pintype "power_in"))
      (node (ref "LEDDRV13") (pin "P$8") (pinfunction "GND_P$8") (pintype "power_in"))
      (node (ref "LEDDRV21") (pin "2") (pinfunction "PGND_2") (pintype "passive"))
      (node (ref "LEDDRV21") (pin "4") (pinfunction "GND_4") (pintype "power_in"))
      (node (ref "LEDDRV21") (pin "EPAD") (pinfunction "GND_EPAD") (pintype "power_in"))
      (node (ref "LEDDRV21") (pin "P$1") (pinfunction "GND_P$1") (pintype "power_in"))
      (node (ref "LEDDRV21") (pin "P$2") (pinfunction "GND_P$2") (pintype "power_in"))
      (node (ref "LEDDRV21") (pin "P$3") (pinfunction "GND_P$3") (pintype "power_in"))
      (node (ref "LEDDRV21") (pin "P$4") (pinfunction "GND_P$4") (pintype "power_in"))
      (node (ref "LEDDRV21") (pin "P$5") (pinfunction "GND_P$5") (pintype "power_in"))
      (node (ref "LEDDRV21") (pin "P$6") (pinfunction "GND_P$6") (pintype "power_in"))
      (node (ref "LEDDRV21") (pin "P$7") (pinfunction "GND_P$7") (pintype "power_in"))
      (node (ref "LEDDRV21") (pin "P$8") (pinfunction "GND_P$8") (pintype "power_in"))
      (node (ref "LEDDRV22") (pin "2") (pinfunction "PGND_2") (pintype "passive"))
      (node (ref "LEDDRV22") (pin "4") (pinfunction "GND_4") (pintype "power_in"))
      (node (ref "LEDDRV22") (pin "EPAD") (pinfunction "GND_EPAD") (pintype "power_in"))
      (node (ref "LEDDRV22") (pin "P$1") (pinfunction "GND_P$1") (pintype "power_in"))
      (node (ref "LEDDRV22") (pin "P$2") (pinfunction "GND_P$2") (pintype "power_in"))
      (node (ref "LEDDRV22") (pin "P$3") (pinfunction "GND_P$3") (pintype "power_in"))
      (node (ref "LEDDRV22") (pin "P$4") (pinfunction "GND_P$4") (pintype "power_in"))
      (node (ref "LEDDRV22") (pin "P$5") (pinfunction "GND_P$5") (pintype "power_in"))
      (node (ref "LEDDRV22") (pin "P$6") (pinfunction "GND_P$6") (pintype "power_in"))
      (node (ref "LEDDRV22") (pin "P$7") (pinfunction "GND_P$7") (pintype "power_in"))
      (node (ref "LEDDRV22") (pin "P$8") (pinfunction "GND_P$8") (pintype "power_in"))
      (node (ref "LEDDRV23") (pin "2") (pinfunction "PGND_2") (pintype "passive"))
      (node (ref "LEDDRV23") (pin "4") (pinfunction "GND_4") (pintype "power_in"))
      (node (ref "LEDDRV23") (pin "EPAD") (pinfunction "GND_EPAD") (pintype "power_in"))
      (node (ref "LEDDRV23") (pin "P$1") (pinfunction "GND_P$1") (pintype "power_in"))
      (node (ref "LEDDRV23") (pin "P$2") (pinfunction "GND_P$2") (pintype "power_in"))
      (node (ref "LEDDRV23") (pin "P$3") (pinfunction "GND_P$3") (pintype "power_in"))
      (node (ref "LEDDRV23") (pin "P$4") (pinfunction "GND_P$4") (pintype "power_in"))
      (node (ref "LEDDRV23") (pin "P$5") (pinfunction "GND_P$5") (pintype "power_in"))
      (node (ref "LEDDRV23") (pin "P$6") (pinfunction "GND_P$6") (pintype "power_in"))
      (node (ref "LEDDRV23") (pin "P$7") (pinfunction "GND_P$7") (pintype "power_in"))
      (node (ref "LEDDRV23") (pin "P$8") (pinfunction "GND_P$8") (pintype "power_in"))
      (node (ref "LEDDRV31") (pin "2") (pinfunction "PGND_2") (pintype "passive"))
      (node (ref "LEDDRV31") (pin "4") (pinfunction "GND_4") (pintype "power_in"))
      (node (ref "LEDDRV31") (pin "EPAD") (pinfunction "GND_EPAD") (pintype "power_in"))
      (node (ref "LEDDRV31") (pin "P$1") (pinfunction "GND_P$1") (pintype "power_in"))
      (node (ref "LEDDRV31") (pin "P$2") (pinfunction "GND_P$2") (pintype "power_in"))
      (node (ref "LEDDRV31") (pin "P$3") (pinfunction "GND_P$3") (pintype "power_in"))
      (node (ref "LEDDRV31") (pin "P$4") (pinfunction "GND_P$4") (pintype "power_in"))
      (node (ref "LEDDRV31") (pin "P$5") (pinfunction "GND_P$5") (pintype "power_in"))
      (node (ref "LEDDRV31") (pin "P$6") (pinfunction "GND_P$6") (pintype "power_in"))
      (node (ref "LEDDRV31") (pin "P$7") (pinfunction "GND_P$7") (pintype "power_in"))
      (node (ref "LEDDRV31") (pin "P$8") (pinfunction "GND_P$8") (pintype "power_in"))
      (node (ref "LEDDRV32") (pin "2") (pinfunction "PGND_2") (pintype "passive"))
      (node (ref "LEDDRV32") (pin "4") (pinfunction "GND_4") (pintype "power_in"))
      (node (ref "LEDDRV32") (pin "EPAD") (pinfunction "GND_EPAD") (pintype "power_in"))
      (node (ref "LEDDRV32") (pin "P$1") (pinfunction "GND_P$1") (pintype "power_in"))
      (node (ref "LEDDRV32") (pin "P$2") (pinfunction "GND_P$2") (pintype "power_in"))
      (node (ref "LEDDRV32") (pin "P$3") (pinfunction "GND_P$3") (pintype "power_in"))
      (node (ref "LEDDRV32") (pin "P$4") (pinfunction "GND_P$4") (pintype "power_in"))
      (node (ref "LEDDRV32") (pin "P$5") (pinfunction "GND_P$5") (pintype "power_in"))
      (node (ref "LEDDRV32") (pin "P$6") (pinfunction "GND_P$6") (pintype "power_in"))
      (node (ref "LEDDRV32") (pin "P$7") (pinfunction "GND_P$7") (pintype "power_in"))
      (node (ref "LEDDRV32") (pin "P$8") (pinfunction "GND_P$8") (pintype "power_in"))
      (node (ref "LEDDRV33") (pin "2") (pinfunction "PGND_2") (pintype "passive"))
      (node (ref "LEDDRV33") (pin "4") (pinfunction "GND_4") (pintype "power_in"))
      (node (ref "LEDDRV33") (pin "EPAD") (pinfunction "GND_EPAD") (pintype "power_in"))
      (node (ref "LEDDRV33") (pin "P$1") (pinfunction "GND_P$1") (pintype "power_in"))
      (node (ref "LEDDRV33") (pin "P$2") (pinfunction "GND_P$2") (pintype "power_in"))
      (node (ref "LEDDRV33") (pin "P$3") (pinfunction "GND_P$3") (pintype "power_in"))
      (node (ref "LEDDRV33") (pin "P$4") (pinfunction "GND_P$4") (pintype "power_in"))
      (node (ref "LEDDRV33") (pin "P$5") (pinfunction "GND_P$5") (pintype "power_in"))
      (node (ref "LEDDRV33") (pin "P$6") (pinfunction "GND_P$6") (pintype "power_in"))
      (node (ref "LEDDRV33") (pin "P$7") (pinfunction "GND_P$7") (pintype "power_in"))
      (node (ref "LEDDRV33") (pin "P$8") (pinfunction "GND_P$8") (pintype "power_in"))
      (node (ref "LEDDRV41") (pin "2") (pinfunction "PGND_2") (pintype "passive"))
      (node (ref "LEDDRV41") (pin "4") (pinfunction "GND_4") (pintype "power_in"))
      (node (ref "LEDDRV41") (pin "EPAD") (pinfunction "GND_EPAD") (pintype "power_in"))
      (node (ref "LEDDRV41") (pin "P$1") (pinfunction "GND_P$1") (pintype "power_in"))
      (node (ref "LEDDRV41") (pin "P$2") (pinfunction "GND_P$2") (pintype "power_in"))
      (node (ref "LEDDRV41") (pin "P$3") (pinfunction "GND_P$3") (pintype "power_in"))
      (node (ref "LEDDRV41") (pin "P$4") (pinfunction "GND_P$4") (pintype "power_in"))
      (node (ref "LEDDRV41") (pin "P$5") (pinfunction "GND_P$5") (pintype "power_in"))
      (node (ref "LEDDRV41") (pin "P$6") (pinfunction "GND_P$6") (pintype "power_in"))
      (node (ref "LEDDRV41") (pin "P$7") (pinfunction "GND_P$7") (pintype "power_in"))
      (node (ref "LEDDRV41") (pin "P$8") (pinfunction "GND_P$8") (pintype "power_in"))
      (node (ref "LEDDRV42") (pin "2") (pinfunction "PGND_2") (pintype "passive"))
      (node (ref "LEDDRV42") (pin "4") (pinfunction "GND_4") (pintype "power_in"))
      (node (ref "LEDDRV42") (pin "EPAD") (pinfunction "GND_EPAD") (pintype "power_in"))
      (node (ref "LEDDRV42") (pin "P$1") (pinfunction "GND_P$1") (pintype "power_in"))
      (node (ref "LEDDRV42") (pin "P$2") (pinfunction "GND_P$2") (pintype "power_in"))
      (node (ref "LEDDRV42") (pin "P$3") (pinfunction "GND_P$3") (pintype "power_in"))
      (node (ref "LEDDRV42") (pin "P$4") (pinfunction "GND_P$4") (pintype "power_in"))
      (node (ref "LEDDRV42") (pin "P$5") (pinfunction "GND_P$5") (pintype "power_in"))
      (node (ref "LEDDRV42") (pin "P$6") (pinfunction "GND_P$6") (pintype "power_in"))
      (node (ref "LEDDRV42") (pin "P$7") (pinfunction "GND_P$7") (pintype "power_in"))
      (node (ref "LEDDRV42") (pin "P$8") (pinfunction "GND_P$8") (pintype "power_in"))
      (node (ref "LEDDRV43") (pin "2") (pinfunction "PGND_2") (pintype "passive"))
      (node (ref "LEDDRV43") (pin "4") (pinfunction "GND_4") (pintype "power_in"))
      (node (ref "LEDDRV43") (pin "EPAD") (pinfunction "GND_EPAD") (pintype "power_in"))
      (node (ref "LEDDRV43") (pin "P$1") (pinfunction "GND_P$1") (pintype "power_in"))
      (node (ref "LEDDRV43") (pin "P$2") (pinfunction "GND_P$2") (pintype "power_in"))
      (node (ref "LEDDRV43") (pin "P$3") (pinfunction "GND_P$3") (pintype "power_in"))
      (node (ref "LEDDRV43") (pin "P$4") (pinfunction "GND_P$4") (pintype "power_in"))
      (node (ref "LEDDRV43") (pin "P$5") (pinfunction "GND_P$5") (pintype "power_in"))
      (node (ref "LEDDRV43") (pin "P$6") (pinfunction "GND_P$6") (pintype "power_in"))
      (node (ref "LEDDRV43") (pin "P$7") (pinfunction "GND_P$7") (pintype "power_in"))
      (node (ref "LEDDRV43") (pin "P$8") (pinfunction "GND_P$8") (pintype "power_in"))
      (node (ref "Q3") (pin "2") (pinfunction "S_2") (pintype "passive"))
      (node (ref "R1") (pin "1") (pinfunction "1_1") (pintype "passive"))
      (node (ref "R10") (pin "1") (pinfunction "1_1") (pintype "passive"))
      (node (ref "R12") (pin "1") (pinfunction "1_1") (pintype "passive"))
      (node (ref "R14") (pin "1") (pinfunction "1_1") (pintype "passive"))
      (node (ref "R15") (pin "1") (pinfunction "1_1") (pintype "passive"))
      (node (ref "R16") (pin "1") (pinfunction "1_1") (pintype "passive"))
      (node (ref "R17") (pin "1") (pinfunction "1_1") (pintype "passive"))
      (node (ref "R18") (pin "1") (pinfunction "1_1") (pintype "passive"))
      (node (ref "R19") (pin "1") (pinfunction "1_1") (pintype "passive"))
      (node (ref "R2") (pin "1") (pinfunction "1_1") (pintype "passive"))
      (node (ref "R20") (pin "1") (pinfunction "1_1") (pintype "passive"))
      (node (ref "R21") (pin "1") (pinfunction "1_1") (pintype "passive"))
      (node (ref "R22") (pin "1") (pinfunction "1_1") (pintype "passive"))
      (node (ref "R23") (pin "1") (pinfunction "1_1") (pintype "passive"))
      (node (ref "R25") (pin "1") (pinfunction "1_1") (pintype "passive"))
      (node (ref "R26") (pin "1") (pinfunction "1_1") (pintype "passive"))
      (node (ref "R27") (pin "1") (pinfunction "1_1") (pintype "passive"))
      (node (ref "R28") (pin "1") (pinfunction "1_1") (pintype "passive"))
      (node (ref "R29") (pin "1") (pinfunction "1_1") (pintype "passive"))
      (node (ref "R30") (pin "1") (pinfunction "1_1") (pintype "passive"))
      (node (ref "R31") (pin "1") (pinfunction "1_1") (pintype "passive"))
      (node (ref "R32") (pin "1") (pinfunction "1_1") (pintype "passive"))
      (node (ref "R34") (pin "1") (pinfunction "1_1") (pintype "passive"))
      (node (ref "R35") (pin "1") (pinfunction "1_1") (pintype "passive"))
      (node (ref "R37") (pin "1") (pinfunction "1_1") (pintype "passive"))
      (node (ref "R4") (pin "2") (pinfunction "2_2") (pintype "passive"))
      (node (ref "R43") (pin "1") (pinfunction "1_1") (pintype "passive"))
      (node (ref "R44") (pin "1") (pinfunction "1_1") (pintype "passive"))
      (node (ref "R45") (pin "1") (pinfunction "1_1") (pintype "passive"))
      (node (ref "R46") (pin "1") (pinfunction "1_1") (pintype "passive"))
      (node (ref "R47") (pin "1") (pinfunction "1_1") (pintype "passive"))
      (node (ref "R48") (pin "1") (pinfunction "1_1") (pintype "passive"))
      (node (ref "R49") (pin "1") (pinfunction "1_1") (pintype "passive"))
      (node (ref "R5") (pin "2") (pinfunction "2_2") (pintype "passive"))
      (node (ref "R50") (pin "1") (pinfunction "1_1") (pintype "passive"))
      (node (ref "R51") (pin "1") (pinfunction "1_1") (pintype "passive"))
      (node (ref "R52") (pin "1") (pinfunction "1_1") (pintype "passive"))
      (node (ref "R53") (pin "1") (pinfunction "1_1") (pintype "passive"))
      (node (ref "R54") (pin "1") (pinfunction "1_1") (pintype "passive"))
      (node (ref "R55") (pin "1") (pinfunction "1_1") (pintype "passive"))
      (node (ref "R56") (pin "1") (pinfunction "1_1") (pintype "passive"))
      (node (ref "R57") (pin "1") (pinfunction "1_1") (pintype "passive"))
      (node (ref "R58") (pin "1") (pinfunction "1_1") (pintype "passive"))
      (node (ref "R59") (pin "1") (pinfunction "1_1") (pintype "passive"))
      (node (ref "R60") (pin "1") (pinfunction "1_1") (pintype "passive"))
      (node (ref "R63") (pin "1") (pinfunction "1_1") (pintype "passive"))
      (node (ref "R64") (pin "1") (pinfunction "1_1") (pintype "passive"))
      (node (ref "R65") (pin "1") (pinfunction "1_1") (pintype "passive"))
      (node (ref "R7") (pin "1") (pinfunction "1_1") (pintype "passive"))
      (node (ref "R9") (pin "1") (pinfunction "1_1") (pintype "passive"))
      (node (ref "TP1") (pin "TP") (pinfunction "TP_TP") (pintype "input"))
      (node (ref "TP2") (pin "TP") (pinfunction "TP_TP") (pintype "input"))
      (node (ref "U1") (pin "2") (pinfunction "2_2") (pintype "passive"))
      (node (ref "U2") (pin "2") (pinfunction "GND_2") (pintype "bidirectional"))
      (node (ref "U5") (pin "2") (pinfunction "GND_2") (pintype "bidirectional"))
      (node (ref "X2") (pin "2") (pinfunction "OUT_2") (pintype "bidirectional"))
      (node (ref "X3") (pin "1") (pinfunction "1_1") (pintype "passive"))
      (node (ref "X3") (pin "2") (pinfunction "2_2") (pintype "passive"))
    )
    (net (code "9") (name "LED11_IN") (class "Default")
      (node (ref "C27") (pin "2") (pinfunction "2_2") (pintype "passive"))
      (node (ref "L2") (pin "2") (pinfunction "2_2") (pintype "passive"))
      (node (ref "X1") (pin "12-1") (pinfunction "12_12-1") (pintype "bidirectional"))
      (node (ref "X1") (pin "12-2") (pinfunction "12_12-2") (pintype "bidirectional"))
    )
    (net (code "10") (name "LED12_IN") (class "Default")
      (node (ref "C28") (pin "2") (pinfunction "2_2") (pintype "passive"))
      (node (ref "L3") (pin "2") (pinfunction "2_2") (pintype "passive"))
      (node (ref "X1") (pin "11-1") (pinfunction "11_11-1") (pintype "bidirectional"))
      (node (ref "X1") (pin "11-2") (pinfunction "11_11-2") (pintype "bidirectional"))
    )
    (net (code "11") (name "LED13_IN") (class "Default")
      (node (ref "C29") (pin "2") (pinfunction "2_2") (pintype "passive"))
      (node (ref "L4") (pin "2") (pinfunction "2_2") (pintype "passive"))
      (node (ref "X1") (pin "10-1") (pinfunction "10_10-1") (pintype "bidirectional"))
      (node (ref "X1") (pin "10-2") (pinfunction "10_10-2") (pintype "bidirectional"))
    )
    (net (code "12") (name "LED21_IN") (class "Default")
      (node (ref "C30") (pin "2") (pinfunction "2_2") (pintype "passive"))
      (node (ref "L5") (pin "2") (pinfunction "2_2") (pintype "passive"))
      (node (ref "X1") (pin "9-1") (pinfunction "9_9-1") (pintype "bidirectional"))
      (node (ref "X1") (pin "9-2") (pinfunction "9_9-2") (pintype "bidirectional"))
    )
    (net (code "13") (name "LED22_IN") (class "Default")
      (node (ref "C31") (pin "2") (pinfunction "2_2") (pintype "passive"))
      (node (ref "L9") (pin "2") (pinfunction "2_2") (pintype "passive"))
      (node (ref "X1") (pin "8-1") (pinfunction "8_8-1") (pintype "bidirectional"))
      (node (ref "X1") (pin "8-2") (pinfunction "8_8-2") (pintype "bidirectional"))
    )
    (net (code "14") (name "LED23_IN") (class "Default")
      (node (ref "C32") (pin "2") (pinfunction "2_2") (pintype "passive"))
      (node (ref "L7") (pin "2") (pinfunction "2_2") (pintype "passive"))
      (node (ref "X1") (pin "7-1") (pinfunction "7_7-1") (pintype "bidirectional"))
      (node (ref "X1") (pin "7-2") (pinfunction "7_7-2") (pintype "bidirectional"))
    )
    (net (code "15") (name "LED31_IN") (class "Default")
      (node (ref "C33") (pin "2") (pinfunction "2_2") (pintype "passive"))
      (node (ref "L6") (pin "2") (pinfunction "2_2") (pintype "passive"))
      (node (ref "X1") (pin "6-1") (pinfunction "6_6-1") (pintype "bidirectional"))
      (node (ref "X1") (pin "6-2") (pinfunction "6_6-2") (pintype "bidirectional"))
    )
    (net (code "16") (name "LED32_IN") (class "Default")
      (node (ref "C35") (pin "2") (pinfunction "2_2") (pintype "passive"))
      (node (ref "L11") (pin "2") (pinfunction "2_2") (pintype "passive"))
      (node (ref "X1") (pin "5-1") (pinfunction "5_5-1") (pintype "bidirectional"))
      (node (ref "X1") (pin "5-2") (pinfunction "5_5-2") (pintype "bidirectional"))
    )
    (net (code "17") (name "LED33_IN") (class "Default")
      (node (ref "C36") (pin "2") (pinfunction "2_2") (pintype "passive"))
      (node (ref "L16") (pin "2") (pinfunction "2_2") (pintype "passive"))
      (node (ref "X1") (pin "4-1") (pinfunction "4_4-1") (pintype "bidirectional"))
      (node (ref "X1") (pin "4-2") (pinfunction "4_4-2") (pintype "bidirectional"))
    )
    (net (code "18") (name "LED41_IN") (class "Default")
      (node (ref "C37") (pin "2") (pinfunction "2_2") (pintype "passive"))
      (node (ref "L8") (pin "2") (pinfunction "2_2") (pintype "passive"))
      (node (ref "X1") (pin "3-1") (pinfunction "3_3-1") (pintype "bidirectional"))
      (node (ref "X1") (pin "3-2") (pinfunction "3_3-2") (pintype "bidirectional"))
    )
    (net (code "19") (name "LED42_IN") (class "Default")
      (node (ref "C38") (pin "2") (pinfunction "2_2") (pintype "passive"))
      (node (ref "L10") (pin "2") (pinfunction "2_2") (pintype "passive"))
      (node (ref "X1") (pin "2-1") (pinfunction "2_2-1") (pintype "bidirectional"))
      (node (ref "X1") (pin "2-2") (pinfunction "2_2-2") (pintype "bidirectional"))
    )
    (net (code "20") (name "LED43_IN") (class "Default")
      (node (ref "C39") (pin "2") (pinfunction "2_2") (pintype "passive"))
      (node (ref "L14") (pin "2") (pinfunction "2_2") (pintype "passive"))
      (node (ref "X1") (pin "1-1") (pinfunction "1_1-1") (pintype "bidirectional"))
      (node (ref "X1") (pin "1-2") (pinfunction "1_1-2") (pintype "bidirectional"))
    )
    (net (code "21") (name "LED_ENABLE") (class "Default")
      (node (ref "IC1") (pin "2") (pinfunction "PC14-OSC32_IN_2") (pintype "bidirectional"))
      (node (ref "R24") (pin "2") (pinfunction "2_2") (pintype "passive"))
    )
    (net (code "22") (name "LED_PWR") (class "Default")
      (node (ref "C18") (pin "1") (pinfunction "1_1") (pintype "passive"))
      (node (ref "C27") (pin "1") (pinfunction "1_1") (pintype "passive"))
      (node (ref "C28") (pin "1") (pinfunction "1_1") (pintype "passive"))
      (node (ref "C29") (pin "1") (pinfunction "1_1") (pintype "passive"))
      (node (ref "C30") (pin "1") (pinfunction "1_1") (pintype "passive"))
      (node (ref "C31") (pin "1") (pinfunction "1_1") (pintype "passive"))
      (node (ref "C32") (pin "1") (pinfunction "1_1") (pintype "passive"))
      (node (ref "C33") (pin "1") (pinfunction "1_1") (pintype "passive"))
      (node (ref "C35") (pin "1") (pinfunction "1_1") (pintype "passive"))
      (node (ref "C36") (pin "1") (pinfunction "1_1") (pintype "passive"))
      (node (ref "C37") (pin "1") (pinfunction "1_1") (pintype "passive"))
      (node (ref "C38") (pin "1") (pinfunction "1_1") (pintype "passive"))
      (node (ref "C39") (pin "1") (pinfunction "1_1") (pintype "passive"))
      (node (ref "D10") (pin "C") (pinfunction "C_C") (pintype "passive"))
      (node (ref "D11") (pin "C") (pinfunction "C_C") (pintype "passive"))
      (node (ref "D13") (pin "C") (pinfunction "C_C") (pintype "passive"))
      (node (ref "D15") (pin "C") (pinfunction "C_C") (pintype "passive"))
      (node (ref "D2") (pin "C") (pinfunction "C_C") (pintype "passive"))
      (node (ref "D3") (pin "C") (pinfunction "C_C") (pintype "passive"))
      (node (ref "D4") (pin "C") (pinfunction "C_C") (pintype "passive"))
      (node (ref "D5") (pin "C") (pinfunction "C_C") (pintype "passive"))
      (node (ref "D6") (pin "C") (pinfunction "C_C") (pintype "passive"))
      (node (ref "D7") (pin "C") (pinfunction "C_C") (pintype "passive"))
      (node (ref "D8") (pin "C") (pinfunction "C_C") (pintype "passive"))
      (node (ref "D9") (pin "C") (pinfunction "C_C") (pintype "passive"))
      (node (ref "L1") (pin "2") (pinfunction "2_2") (pintype "passive"))
      (node (ref "LEDDRV11") (pin "8") (pinfunction "VIN_8") (pintype "input"))
      (node (ref "LEDDRV12") (pin "8") (pinfunction "VIN_8") (pintype "input"))
      (node (ref "LEDDRV13") (pin "8") (pinfunction "VIN_8") (pintype "input"))
      (node (ref "LEDDRV21") (pin "8") (pinfunction "VIN_8") (pintype "input"))
      (node (ref "LEDDRV22") (pin "8") (pinfunction "VIN_8") (pintype "input"))
      (node (ref "LEDDRV23") (pin "8") (pinfunction "VIN_8") (pintype "input"))
      (node (ref "LEDDRV31") (pin "8") (pinfunction "VIN_8") (pintype "input"))
      (node (ref "LEDDRV32") (pin "8") (pinfunction "VIN_8") (pintype "input"))
      (node (ref "LEDDRV33") (pin "8") (pinfunction "VIN_8") (pintype "input"))
      (node (ref "LEDDRV41") (pin "8") (pinfunction "VIN_8") (pintype "input"))
      (node (ref "LEDDRV42") (pin "8") (pinfunction "VIN_8") (pintype "input"))
      (node (ref "LEDDRV43") (pin "8") (pinfunction "VIN_8") (pintype "input"))
      (node (ref "X1") (pin "13-1") (pinfunction "13_13-1") (pintype "bidirectional"))
      (node (ref "X1") (pin "13-2") (pinfunction "13_13-2") (pintype "bidirectional"))
      (node (ref "X1") (pin "14-1") (pinfunction "14_14-1") (pintype "bidirectional"))
      (node (ref "X1") (pin "14-2") (pinfunction "14_14-2") (pintype "bidirectional"))
      (node (ref "X1") (pin "15-1") (pinfunction "15_15-1") (pintype "bidirectional"))
      (node (ref "X1") (pin "15-2") (pinfunction "15_15-2") (pintype "bidirectional"))
      (node (ref "X1") (pin "16-1") (pinfunction "16_16-1") (pintype "bidirectional"))
      (node (ref "X1") (pin "16-2") (pinfunction "16_16-2") (pintype "bidirectional"))
      (node (ref "X1") (pin "17-1") (pinfunction "17_17-1") (pintype "bidirectional"))
      (node (ref "X1") (pin "17-2") (pinfunction "17_17-2") (pintype "bidirectional"))
      (node (ref "X1") (pin "18-1") (pinfunction "18_18-1") (pintype "bidirectional"))
      (node (ref "X1") (pin "18-2") (pinfunction "18_18-2") (pintype "bidirectional"))
      (node (ref "X1") (pin "19-1") (pinfunction "19_19-1") (pintype "bidirectional"))
      (node (ref "X1") (pin "19-2") (pinfunction "19_19-2") (pintype "bidirectional"))
      (node (ref "X1") (pin "20-1") (pinfunction "20_20-1") (pintype "bidirectional"))
      (node (ref "X1") (pin "20-2") (pinfunction "20_20-2") (pintype "bidirectional"))
    )
    (net (code "23") (name "Net-(GROUNDING-MOUNT)") (class "Default")
      (node (ref "GROUNDING") (pin "B3,0") (pinfunction "MOUNT_B3,0") (pintype "passive"))
      (node (ref "R1") (pin "2") (pinfunction "2_2") (pintype "passive"))
    )
    (net (code "24") (name "Net-(IC1-BOOT0-PH3)") (class "Default")
      (node (ref "IC1") (pin "31") (pinfunction "BOOT0-PH3_31") (pintype "bidirectional"))
      (node (ref "R7") (pin "2") (pinfunction "2_2") (pintype "passive"))
    )
    (net (code "25") (name "Net-(IC3-INTVCC)") (class "Default")
      (node (ref "C23") (pin "2") (pinfunction "2_2") (pintype "passive"))
      (node (ref "IC3") (pin "2") (pinfunction "INTVCC_2") (pintype "passive"))
    )
    (net (code "26") (name "Net-(IC3-SENSE+)") (class "Default")
      (node (ref "F2") (pin "1") (pinfunction "1_1") (pintype "passive"))
      (node (ref "IC3") (pin "1") (pinfunction "VDD_1") (pintype "passive"))
      (node (ref "IC3") (pin "12") (pinfunction "SENSE+_12") (pintype "input"))
      (node (ref "R8") (pin "1") (pinfunction "1_1") (pintype "passive"))
    )
    (net (code "27") (name "Net-(IC3-SENSE-)") (class "Default")
      (node (ref "C25") (pin "1") (pinfunction "1_1") (pintype "passive"))
      (node (ref "IC3") (pin "11") (pinfunction "SENSE-_11") (pintype "input"))
      (node (ref "L1") (pin "1") (pinfunction "1_1") (pintype "passive"))
      (node (ref "R8") (pin "2") (pinfunction "2_2") (pintype "passive"))
    )
    (net (code "28") (name "Net-(IC5-GATE)") (class "Default")
      (node (ref "IC5") (pin "8") (pinfunction "GATE_8") (pintype "output"))
      (node (ref "IC6") (pin "1") (pinfunction "G_1") (pintype "passive"))
      (node (ref "IC6") (pin "3") (pinfunction "G_3") (pintype "passive"))
    )
    (net (code "29") (name "Net-(IC5-OV)") (class "Default")
      (node (ref "IC5") (pin "3") (pinfunction "OV_3") (pintype "input"))
      (node (ref "R33") (pin "1") (pinfunction "1_1") (pintype "passive"))
      (node (ref "R34") (pin "2") (pinfunction "2_2") (pintype "passive"))
    )
    (net (code "30") (name "Net-(IC5-UV)") (class "Default")
      (node (ref "IC5") (pin "2") (pinfunction "UV_2") (pintype "input"))
      (node (ref "R33") (pin "2") (pinfunction "2_2") (pintype "passive"))
      (node (ref "R40") (pin "1") (pinfunction "1_1") (pintype "passive"))
    )
    (net (code "31") (name "Net-(IC5-VIN)") (class "Default")
      (node (ref "C1") (pin "+") (pinfunction "+_+") (pintype "passive"))
      (node (ref "C3") (pin "1") (pinfunction "1_1") (pintype "passive"))
      (node (ref "C4") (pin "1") (pinfunction "1_1") (pintype "passive"))
      (node (ref "F3") (pin "1") (pinfunction "1_1") (pintype "passive"))
      (node (ref "IC5") (pin "1") (pinfunction "VIN_1") (pintype "passive"))
      (node (ref "IC6") (pin "6") (pinfunction "D_6") (pintype "passive"))
      (node (ref "R2") (pin "2") (pinfunction "2_2") (pintype "passive"))
      (node (ref "R39") (pin "2") (pinfunction "2_2") (pintype "passive"))
      (node (ref "R40") (pin "2") (pinfunction "2_2") (pintype "passive"))
    )
    (net (code "32") (name "Net-(IC5-~{SHDN})") (class "Default")
      (node (ref "IC5") (pin "5") (pinfunction "~{SHDN}_5") (pintype "input"))
      (node (ref "R39") (pin "1") (pinfunction "1_1") (pintype "passive"))
    )
    (net (code "33") (name "Net-(IC6A-S)") (class "Default")
      (node (ref "IC6") (pin "2") (pinfunction "S_2") (pintype "passive"))
      (node (ref "IC6") (pin "5") (pinfunction "S_5") (pintype "passive"))
    )
    (net (code "34") (name "Net-(J1-CC1)") (class "Default")
      (node (ref "J1") (pin "A5") (pinfunction "CC1_A5") (pintype "bidirectional"))
      (node (ref "R10") (pin "2") (pinfunction "2_2") (pintype "passive"))
    )
    (net (code "35") (name "Net-(J1-CC2)") (class "Default")
      (node (ref "J1") (pin "B5") (pinfunction "CC2_B5") (pintype "bidirectional"))
      (node (ref "R9") (pin "2") (pinfunction "2_2") (pintype "passive"))
    )
    (net (code "36") (name "Net-(J1-DN-PadA7)") (class "Default")
      (node (ref "J1") (pin "A7") (pinfunction "DN_A7") (pintype "bidirectional"))
      (node (ref "J1") (pin "B7") (pinfunction "DN_B7") (pintype "bidirectional"))
      (node (ref "U1") (pin "1") (pinfunction "1_1") (pintype "bidirectional"))
    )
    (net (code "37") (name "Net-(J1-DP-PadA6)") (class "Default")
      (node (ref "J1") (pin "A6") (pinfunction "DP_A6") (pintype "bidirectional"))
      (node (ref "J1") (pin "B6") (pinfunction "DP_B6") (pintype "bidirectional"))
      (node (ref "U1") (pin "3") (pinfunction "3_3") (pintype "bidirectional"))
    )
    (net (code "38") (name "Net-(J1-SHLD-PadP1)") (class "Default")
      (node (ref "J1") (pin "P1") (pinfunction "SHLD_P1") (pintype "bidirectional"))
      (node (ref "J1") (pin "P2") (pinfunction "SHLD_P2") (pintype "bidirectional"))
      (node (ref "J1") (pin "P3") (pinfunction "SHLD_P3") (pintype "bidirectional"))
      (node (ref "J1") (pin "P4") (pinfunction "SHLD_P4") (pintype "bidirectional"))
      (node (ref "J1") (pin "S1") (pinfunction "SHLD_S1") (pintype "bidirectional"))
      (node (ref "J1") (pin "S2") (pinfunction "SHLD_S2") (pintype "bidirectional"))
      (node (ref "J1") (pin "S3") (pinfunction "SHLD_S3") (pintype "bidirectional"))
      (node (ref "J1") (pin "S4") (pinfunction "SHLD_S4") (pintype "bidirectional"))
      (node (ref "J1") (pin "S5") (pinfunction "SHLD_S5") (pintype "bidirectional"))
      (node (ref "J1") (pin "S6") (pinfunction "SHLD_S6") (pintype "bidirectional"))
      (node (ref "J1") (pin "S7") (pinfunction "SHLD_S7") (pintype "bidirectional"))
      (node (ref "J1") (pin "S8") (pinfunction "SHLD_S8") (pintype "bidirectional"))
      (node (ref "R32") (pin "2") (pinfunction "2_2") (pintype "passive"))
    )
    (net (code "39") (name "Net-(L13-1)") (class "Default")
      (node (ref "L13") (pin "P$1") (pinfunction "1_P$1") (pintype "passive"))
      (node (ref "U5") (pin "3") (pinfunction "PH_3") (pintype "bidirectional"))
    )
    (net (code "40") (name "Net-(L13-2)") (class "Default")
      (node (ref "C2") (pin "2") (pinfunction "2_2") (pintype "passive"))
      (node (ref "C40") (pin "2") (pinfunction "2_2") (pintype "passive"))
      (node (ref "L13") (pin "P$2") (pinfunction "2_P$2") (pintype "passive"))
      (node (ref "R11") (pin "2") (pinfunction "2_2") (pintype "passive"))
      (node (ref "U2") (pin "1") (pinfunction "IN_1") (pintype "bidirectional"))
      (node (ref "U2") (pin "3") (pinfunction "EN_3") (pintype "bidirectional"))
    )
    (net (code "41") (name "Net-(LED1-PadA)") (class "Default")
      (node (ref "LED1") (pin "A") (pinfunction "A_A") (pintype "passive"))
      (node (ref "R41") (pin "1") (pinfunction "1_1") (pintype "passive"))
    )
    (net (code "42") (name "Net-(LED2-PadA)") (class "Default")
      (node (ref "LED2") (pin "A") (pinfunction "A_A") (pintype "passive"))
      (node (ref "R42") (pin "1") (pinfunction "1_1") (pintype "passive"))
    )
    (net (code "43") (name "Net-(LEDDRV11-FS)") (class "Default")
      (node (ref "LEDDRV11") (pin "5") (pinfunction "FS_5") (pintype "passive"))
      (node (ref "R57") (pin "2") (pinfunction "2_2") (pintype "passive"))
    )
    (net (code "44") (name "Net-(LEDDRV11-IADJ)") (class "Default")
      (node (ref "LEDDRV11") (pin "3") (pinfunction "IADJ_3") (pintype "passive"))
      (node (ref "R58") (pin "2") (pinfunction "2_2") (pintype "passive"))
    )
    (net (code "45") (name "Net-(LEDDRV11-LX)") (class "Default")
      (node (ref "D2") (pin "A") (pinfunction "A_A") (pintype "passive"))
      (node (ref "L2") (pin "1") (pinfunction "1_1") (pintype "passive"))
      (node (ref "LEDDRV11") (pin "7") (pinfunction "LX_7") (pintype "passive"))
    )
    (net (code "46") (name "Net-(LEDDRV11-VCC)") (class "Default")
      (node (ref "C24") (pin "2") (pinfunction "2_2") (pintype "passive"))
      (node (ref "LEDDRV11") (pin "1") (pinfunction "VCC_1") (pintype "passive"))
    )
    (net (code "47") (name "Net-(LEDDRV12-FS)") (class "Default")
      (node (ref "LEDDRV12") (pin "5") (pinfunction "FS_5") (pintype "passive"))
      (node (ref "R14") (pin "2") (pinfunction "2_2") (pintype "passive"))
    )
    (net (code "48") (name "Net-(LEDDRV12-IADJ)") (class "Default")
      (node (ref "LEDDRV12") (pin "3") (pinfunction "IADJ_3") (pintype "passive"))
      (node (ref "R15") (pin "2") (pinfunction "2_2") (pintype "passive"))
    )
    (net (code "49") (name "Net-(LEDDRV12-LX)") (class "Default")
      (node (ref "D3") (pin "A") (pinfunction "A_A") (pintype "passive"))
      (node (ref "L3") (pin "1") (pinfunction "1_1") (pintype "passive"))
      (node (ref "LEDDRV12") (pin "7") (pinfunction "LX_7") (pintype "passive"))
    )
    (net (code "50") (name "Net-(LEDDRV12-VCC)") (class "Default")
      (node (ref "C7") (pin "2") (pinfunction "2_2") (pintype "passive"))
      (node (ref "LEDDRV12") (pin "1") (pinfunction "VCC_1") (pintype "passive"))
    )
    (net (code "51") (name "Net-(LEDDRV13-FS)") (class "Default")
      (node (ref "LEDDRV13") (pin "5") (pinfunction "FS_5") (pintype "passive"))
      (node (ref "R45") (pin "2") (pinfunction "2_2") (pintype "passive"))
    )
    (net (code "52") (name "Net-(LEDDRV13-IADJ)") (class "Default")
      (node (ref "LEDDRV13") (pin "3") (pinfunction "IADJ_3") (pintype "passive"))
      (node (ref "R46") (pin "2") (pinfunction "2_2") (pintype "passive"))
    )
    (net (code "53") (name "Net-(LEDDRV13-LX)") (class "Default")
      (node (ref "D4") (pin "A") (pinfunction "A_A") (pintype "passive"))
      (node (ref "L4") (pin "1") (pinfunction "1_1") (pintype "passive"))
      (node (ref "LEDDRV13") (pin "7") (pinfunction "LX_7") (pintype "passive"))
    )
    (net (code "54") (name "Net-(LEDDRV13-VCC)") (class "Default")
      (node (ref "C8") (pin "2") (pinfunction "2_2") (pintype "passive"))
      (node (ref "LEDDRV13") (pin "1") (pinfunction "VCC_1") (pintype "passive"))
    )
    (net (code "55") (name "Net-(LEDDRV21-FS)") (class "Default")
      (node (ref "LEDDRV21") (pin "5") (pinfunction "FS_5") (pintype "passive"))
      (node (ref "R17") (pin "2") (pinfunction "2_2") (pintype "passive"))
    )
    (net (code "56") (name "Net-(LEDDRV21-IADJ)") (class "Default")
      (node (ref "LEDDRV21") (pin "3") (pinfunction "IADJ_3") (pintype "passive"))
      (node (ref "R18") (pin "2") (pinfunction "2_2") (pintype "passive"))
    )
    (net (code "57") (name "Net-(LEDDRV21-LX)") (class "Default")
      (node (ref "D5") (pin "A") (pinfunction "A_A") (pintype "passive"))
      (node (ref "L5") (pin "1") (pinfunction "1_1") (pintype "passive"))
      (node (ref "LEDDRV21") (pin "7") (pinfunction "LX_7") (pintype "passive"))
    )
    (net (code "58") (name "Net-(LEDDRV21-VCC)") (class "Default")
      (node (ref "C9") (pin "2") (pinfunction "2_2") (pintype "passive"))
      (node (ref "LEDDRV21") (pin "1") (pinfunction "VCC_1") (pintype "passive"))
    )
    (net (code "59") (name "Net-(LEDDRV22-FS)") (class "Default")
      (node (ref "LEDDRV22") (pin "5") (pinfunction "FS_5") (pintype "passive"))
      (node (ref "R48") (pin "2") (pinfunction "2_2") (pintype "passive"))
    )
    (net (code "60") (name "Net-(LEDDRV22-IADJ)") (class "Default")
      (node (ref "LEDDRV22") (pin "3") (pinfunction "IADJ_3") (pintype "passive"))
      (node (ref "R49") (pin "2") (pinfunction "2_2") (pintype "passive"))
    )
    (net (code "61") (name "Net-(LEDDRV22-LX)") (class "Default")
      (node (ref "D9") (pin "A") (pinfunction "A_A") (pintype "passive"))
      (node (ref "L9") (pin "1") (pinfunction "1_1") (pintype "passive"))
      (node (ref "LEDDRV22") (pin "7") (pinfunction "LX_7") (pintype "passive"))
    )
    (net (code "62") (name "Net-(LEDDRV22-VCC)") (class "Default")
      (node (ref "C13") (pin "2") (pinfunction "2_2") (pintype "passive"))
      (node (ref "LEDDRV22") (pin "1") (pinfunction "VCC_1") (pintype "passive"))
    )
    (net (code "63") (name "Net-(LEDDRV23-FS)") (class "Default")
      (node (ref "LEDDRV23") (pin "5") (pinfunction "FS_5") (pintype "passive"))
      (node (ref "R22") (pin "2") (pinfunction "2_2") (pintype "passive"))
    )
    (net (code "64") (name "Net-(LEDDRV23-IADJ)") (class "Default")
      (node (ref "LEDDRV23") (pin "3") (pinfunction "IADJ_3") (pintype "passive"))
      (node (ref "R26") (pin "2") (pinfunction "2_2") (pintype "passive"))
    )
    (net (code "65") (name "Net-(LEDDRV23-LX)") (class "Default")
      (node (ref "D7") (pin "A") (pinfunction "A_A") (pintype "passive"))
      (node (ref "L7") (pin "1") (pinfunction "1_1") (pintype "passive"))
      (node (ref "LEDDRV23") (pin "7") (pinfunction "LX_7") (pintype "passive"))
    )
    (net (code "66") (name "Net-(LEDDRV23-VCC)") (class "Default")
      (node (ref "C11") (pin "2") (pinfunction "2_2") (pintype "passive"))
      (node (ref "LEDDRV23") (pin "1") (pinfunction "VCC_1") (pintype "passive"))
    )
    (net (code "67") (name "Net-(LEDDRV31-FS)") (class "Default")
      (node (ref "LEDDRV31") (pin "5") (pinfunction "FS_5") (pintype "passive"))
      (node (ref "R19") (pin "2") (pinfunction "2_2") (pintype "passive"))
    )
    (net (code "68") (name "Net-(LEDDRV31-IADJ)") (class "Default")
      (node (ref "LEDDRV31") (pin "3") (pinfunction "IADJ_3") (pintype "passive"))
      (node (ref "R20") (pin "2") (pinfunction "2_2") (pintype "passive"))
    )
    (net (code "69") (name "Net-(LEDDRV31-LX)") (class "Default")
      (node (ref "D6") (pin "A") (pinfunction "A_A") (pintype "passive"))
      (node (ref "L6") (pin "1") (pinfunction "1_1") (pintype "passive"))
      (node (ref "LEDDRV31") (pin "7") (pinfunction "LX_7") (pintype "passive"))
    )
    (net (code "70") (name "Net-(LEDDRV31-VCC)") (class "Default")
      (node (ref "C10") (pin "2") (pinfunction "2_2") (pintype "passive"))
      (node (ref "LEDDRV31") (pin "1") (pinfunction "VCC_1") (pintype "passive"))
    )
    (net (code "71") (name "Net-(LEDDRV32-FS)") (class "Default")
      (node (ref "LEDDRV32") (pin "5") (pinfunction "FS_5") (pintype "passive"))
      (node (ref "R51") (pin "2") (pinfunction "2_2") (pintype "passive"))
    )
    (net (code "72") (name "Net-(LEDDRV32-IADJ)") (class "Default")
      (node (ref "LEDDRV32") (pin "3") (pinfunction "IADJ_3") (pintype "passive"))
      (node (ref "R52") (pin "2") (pinfunction "2_2") (pintype "passive"))
    )
    (net (code "73") (name "Net-(LEDDRV32-LX)") (class "Default")
      (node (ref "D11") (pin "A") (pinfunction "A_A") (pintype "passive"))
      (node (ref "L11") (pin "1") (pinfunction "1_1") (pintype "passive"))
      (node (ref "LEDDRV32") (pin "7") (pinfunction "LX_7") (pintype "passive"))
    )
    (net (code "74") (name "Net-(LEDDRV32-VCC)") (class "Default")
      (node (ref "C17") (pin "2") (pinfunction "2_2") (pintype "passive"))
      (node (ref "LEDDRV32") (pin "1") (pinfunction "VCC_1") (pintype "passive"))
    )
    (net (code "75") (name "Net-(LEDDRV33-FS)") (class "Default")
      (node (ref "LEDDRV33") (pin "5") (pinfunction "FS_5") (pintype "passive"))
      (node (ref "R63") (pin "2") (pinfunction "2_2") (pintype "passive"))
    )
    (net (code "76") (name "Net-(LEDDRV33-IADJ)") (class "Default")
      (node (ref "LEDDRV33") (pin "3") (pinfunction "IADJ_3") (pintype "passive"))
      (node (ref "R64") (pin "2") (pinfunction "2_2") (pintype "passive"))
    )
    (net (code "77") (name "Net-(LEDDRV33-LX)") (class "Default")
      (node (ref "D15") (pin "A") (pinfunction "A_A") (pintype "passive"))
      (node (ref "L16") (pin "1") (pinfunction "1_1") (pintype "passive"))
      (node (ref "LEDDRV33") (pin "7") (pinfunction "LX_7") (pintype "passive"))
    )
    (net (code "78") (name "Net-(LEDDRV33-VCC)") (class "Default")
      (node (ref "C26") (pin "2") (pinfunction "2_2") (pintype "passive"))
      (node (ref "LEDDRV33") (pin "1") (pinfunction "VCC_1") (pintype "passive"))
    )
    (net (code "79") (name "Net-(LEDDRV41-FS)") (class "Default")
      (node (ref "LEDDRV41") (pin "5") (pinfunction "FS_5") (pintype "passive"))
      (node (ref "R25") (pin "2") (pinfunction "2_2") (pintype "passive"))
    )
    (net (code "80") (name "Net-(LEDDRV41-IADJ)") (class "Default")
      (node (ref "LEDDRV41") (pin "3") (pinfunction "IADJ_3") (pintype "passive"))
      (node (ref "R28") (pin "2") (pinfunction "2_2") (pintype "passive"))
    )
    (net (code "81") (name "Net-(LEDDRV41-LX)") (class "Default")
      (node (ref "D8") (pin "A") (pinfunction "A_A") (pintype "passive"))
      (node (ref "L8") (pin "1") (pinfunction "1_1") (pintype "passive"))
      (node (ref "LEDDRV41") (pin "7") (pinfunction "LX_7") (pintype "passive"))
    )
    (net (code "82") (name "Net-(LEDDRV41-VCC)") (class "Default")
      (node (ref "C12") (pin "2") (pinfunction "2_2") (pintype "passive"))
      (node (ref "LEDDRV41") (pin "1") (pinfunction "VCC_1") (pintype "passive"))
    )
    (net (code "83") (name "Net-(LEDDRV42-FS)") (class "Default")
      (node (ref "LEDDRV42") (pin "5") (pinfunction "FS_5") (pintype "passive"))
      (node (ref "R30") (pin "2") (pinfunction "2_2") (pintype "passive"))
    )
    (net (code "84") (name "Net-(LEDDRV42-IADJ)") (class "Default")
      (node (ref "LEDDRV42") (pin "3") (pinfunction "IADJ_3") (pintype "passive"))
      (node (ref "R31") (pin "2") (pinfunction "2_2") (pintype "passive"))
    )
    (net (code "85") (name "Net-(LEDDRV42-LX)") (class "Default")
      (node (ref "D10") (pin "A") (pinfunction "A_A") (pintype "passive"))
      (node (ref "L10") (pin "1") (pinfunction "1_1") (pintype "passive"))
      (node (ref "LEDDRV42") (pin "7") (pinfunction "LX_7") (pintype "passive"))
    )
    (net (code "86") (name "Net-(LEDDRV42-VCC)") (class "Default")
      (node (ref "C14") (pin "2") (pinfunction "2_2") (pintype "passive"))
      (node (ref "LEDDRV42") (pin "1") (pinfunction "VCC_1") (pintype "passive"))
    )
    (net (code "87") (name "Net-(LEDDRV43-FS)") (class "Default")
      (node (ref "LEDDRV43") (pin "5") (pinfunction "FS_5") (pintype "passive"))
      (node (ref "R54") (pin "2") (pinfunction "2_2") (pintype "passive"))
    )
    (net (code "88") (name "Net-(LEDDRV43-IADJ)") (class "Default")
      (node (ref "LEDDRV43") (pin "3") (pinfunction "IADJ_3") (pintype "passive"))
      (node (ref "R55") (pin "2") (pinfunction "2_2") (pintype "passive"))
    )
    (net (code "89") (name "Net-(LEDDRV43-LX)") (class "Default")
      (node (ref "D13") (pin "A") (pinfunction "A_A") (pintype "passive"))
      (node (ref "L14") (pin "1") (pinfunction "1_1") (pintype "passive"))
      (node (ref "LEDDRV43") (pin "7") (pinfunction "LX_7") (pintype "passive"))
    )
    (net (code "90") (name "Net-(LEDDRV43-VCC)") (class "Default")
      (node (ref "C19") (pin "2") (pinfunction "2_2") (pintype "passive"))
      (node (ref "LEDDRV43") (pin "1") (pinfunction "VCC_1") (pintype "passive"))
    )
    (net (code "91") (name "Net-(Q2-D)") (class "Default")
      (node (ref "C34") (pin "1") (pinfunction "1_1") (pintype "passive"))
      (node (ref "C5") (pin "1") (pinfunction "1_1") (pintype "passive"))
      (node (ref "F2") (pin "2") (pinfunction "2_2") (pintype "passive"))
      (node (ref "Q2") (pin "3") (pinfunction "D_3") (pintype "passive"))
      (node (ref "R5") (pin "1") (pinfunction "1_1") (pintype "passive"))
    )
    (net (code "92") (name "Net-(Q2-G)") (class "Default")
      (node (ref "Q2") (pin "1") (pinfunction "G_1") (pintype "passive"))
      (node (ref "R3") (pin "2") (pinfunction "2_2") (pintype "passive"))
      (node (ref "R6") (pin "1") (pinfunction "1_1") (pintype "passive"))
    )
    (net (code "93") (name "Net-(Q3-D)") (class "Default")
      (node (ref "Q3") (pin "3") (pinfunction "D_3") (pintype "passive"))
      (node (ref "R6") (pin "2") (pinfunction "2_2") (pintype "passive"))
    )
    (net (code "94") (name "Net-(Q3-G)") (class "Default")
      (node (ref "Q3") (pin "1") (pinfunction "G_1") (pintype "passive"))
      (node (ref "R24") (pin "1") (pinfunction "1_1") (pintype "passive"))
      (node (ref "R4") (pin "1") (pinfunction "1_1") (pintype "passive"))
    )
    (net (code "95") (name "Net-(R38-Pad2)") (class "Default")
      (node (ref "R38") (pin "2") (pinfunction "2_2") (pintype "passive"))
      (node (ref "X3") (pin "8") (pinfunction "8_8") (pintype "passive"))
    )
    (net (code "96") (name "Net-(R43-Pad2)") (class "Default")
      (node (ref "R43") (pin "2") (pinfunction "2_2") (pintype "passive"))
      (node (ref "X3") (pin "G1") (pinfunction "G1_G1") (pintype "passive"))
    )
    (net (code "97") (name "Net-(R44-Pad2)") (class "Default")
      (node (ref "R44") (pin "2") (pinfunction "2_2") (pintype "passive"))
      (node (ref "X3") (pin "G2") (pinfunction "G2_G2") (pintype "passive"))
    )
    (net (code "98") (name "Net-(SW1-2)") (class "Default")
      (node (ref "F3") (pin "2") (pinfunction "2_2") (pintype "passive"))
      (node (ref "SW1") (pin "P2") (pinfunction "2_P2") (pintype "passive"))
    )
    (net (code "99") (name "Net-(SW1-3)") (class "Default")
      (node (ref "SW1") (pin "P3") (pinfunction "3_P3") (pintype "passive"))
      (node (ref "X2") (pin "1-1") (pinfunction "IN_1-1") (pintype "bidirectional"))
      (node (ref "X2") (pin "1-2") (pinfunction "IN_1-2") (pintype "bidirectional"))
    )
    (net (code "100") (name "Net-(U5-VIN)") (class "Default")
      (node (ref "C16") (pin "2") (pinfunction "2_2") (pintype "passive"))
      (node (ref "F1") (pin "2") (pinfunction "2_2") (pintype "passive"))
      (node (ref "U5") (pin "4") (pinfunction "VIN_4") (pintype "bidirectional"))
    )
    (net (code "101") (name "Net-(U5-VSENSE)") (class "Default")
      (node (ref "R11") (pin "1") (pinfunction "1_1") (pintype "passive"))
      (node (ref "R12") (pin "2") (pinfunction "2_2") (pintype "passive"))
      (node (ref "U5") (pin "5") (pinfunction "VSENSE_5") (pintype "bidirectional"))
    )
    (net (code "102") (name "SCL") (class "Default")
      (node (ref "IC1") (pin "29") (pinfunction "PB6_29") (pintype "bidirectional"))
      (node (ref "IC3") (pin "7") (pinfunction "SCL_7") (pintype "input"))
      (node (ref "R36") (pin "1") (pinfunction "1_1") (pintype "passive"))
    )
    (net (code "103") (name "SDA") (class "Default")
      (node (ref "IC1") (pin "30") (pinfunction "PB7_30") (pintype "bidirectional"))
      (node (ref "IC3") (pin "8") (pinfunction "SDAI_8") (pintype "input"))
      (node (ref "IC3") (pin "9") (pinfunction "SDAO_9") (pintype "open_collector"))
      (node (ref "R13") (pin "1") (pinfunction "1_1") (pintype "passive"))
    )
    (net (code "104") (name "STATUS_BAD") (class "Default")
      (node (ref "IC1") (pin "28") (pinfunction "PB5_28") (pintype "bidirectional"))
      (node (ref "LED1") (pin "K") (pinfunction "C_K") (pintype "passive"))
    )
    (net (code "105") (name "STATUS_GOOD") (class "Default")
      (node (ref "IC1") (pin "27") (pinfunction "PB4_27") (pintype "bidirectional"))
      (node (ref "LED2") (pin "K") (pinfunction "C_K") (pintype "passive"))
    )
    (net (code "106") (name "SWCLK") (class "Default")
      (node (ref "IC1") (pin "24") (pinfunction "PA14_24") (pintype "bidirectional"))
      (node (ref "J2") (pin "4") (pinfunction "4_4") (pintype "passive"))
    )
    (net (code "107") (name "SWDIO") (class "Default")
      (node (ref "IC1") (pin "23") (pinfunction "PA13_23") (pintype "bidirectional"))
      (node (ref "J2") (pin "2") (pinfunction "2_2") (pintype "passive"))
    )
    (net (code "108") (name "TRIGGER_ISO") (class "Default")
      (node (ref "IC1") (pin "13") (pinfunction "PA7_13") (pintype "bidirectional"))
      (node (ref "X3") (pin "3") (pinfunction "3_3") (pintype "passive"))
    )
    (net (code "109") (name "TRIGGER_TTL") (class "Default")
      (node (ref "IC1") (pin "12") (pinfunction "PA6_12") (pintype "bidirectional"))
      (node (ref "X3") (pin "7") (pinfunction "7_7") (pintype "passive"))
    )
    (net (code "110") (name "USB_DM") (class "Default")
      (node (ref "IC1") (pin "21") (pinfunction "PA11_21") (pintype "bidirectional"))
      (node (ref "U1") (pin "6") (pinfunction "6_6") (pintype "bidirectional"))
    )
    (net (code "111") (name "USB_DP") (class "Default")
      (node (ref "IC1") (pin "22") (pinfunction "PA12_22") (pintype "bidirectional"))
      (node (ref "U1") (pin "4") (pinfunction "4_4") (pintype "bidirectional"))
    )
    (net (code "112") (name "VBUS") (class "Default")
      (node (ref "J1") (pin "A4/B9") (pinfunction "VBUS_A4/B9") (pintype "power_in"))
      (node (ref "J1") (pin "B4/A9") (pinfunction "VBUS_B4/A9") (pintype "power_in"))
      (node (ref "U1") (pin "5") (pinfunction "5_5") (pintype "passive"))
    )
    (net (code "113") (name "VCC") (class "Default")
      (node (ref "C20") (pin "1") (pinfunction "1_1") (pintype "passive"))
      (node (ref "C21") (pin "1") (pinfunction "1_1") (pintype "passive"))
      (node (ref "C22") (pin "1") (pinfunction "1_1") (pintype "passive"))
      (node (ref "C41") (pin "2") (pinfunction "2_2") (pintype "passive"))
      (node (ref "C6") (pin "1") (pinfunction "1_1") (pintype "passive"))
      (node (ref "IC1") (pin "1") (pinfunction "VDD_1") (pintype "bidirectional"))
      (node (ref "IC1") (pin "17") (pinfunction "VDD_17") (pintype "bidirectional"))
      (node (ref "IC1") (pin "5") (pinfunction "VDDA/VREF+_5") (pintype "bidirectional"))
      (node (ref "J2") (pin "1") (pinfunction "1_1") (pintype "passive"))
      (node (ref "R13") (pin "2") (pinfunction "2_2") (pintype "passive"))
      (node (ref "R36") (pin "2") (pinfunction "2_2") (pintype "passive"))
      (node (ref "R41") (pin "2") (pinfunction "2_2") (pintype "passive"))
      (node (ref "R42") (pin "2") (pinfunction "2_2") (pintype "passive"))
      (node (ref "U2") (pin "5") (pinfunction "OUT_5") (pintype "bidirectional"))
      (node (ref "X3") (pin "6") (pinfunction "6_6") (pintype "passive"))
    )
    (net (code "114") (name "unconnected-(IC1-PA4-Pad10)") (class "Default")
      (node (ref "IC1") (pin "10") (pinfunction "PA4_10") (pintype "bidirectional"))
    )
    (net (code "115") (name "unconnected-(IC1-PA5-Pad11)") (class "Default")
      (node (ref "IC1") (pin "11") (pinfunction "PA5_11") (pintype "bidirectional"))
    )
    (net (code "116") (name "unconnected-(IC1-PA8-Pad18)") (class "Default")
      (node (ref "IC1") (pin "18") (pinfunction "PA8_18") (pintype "bidirectional"))
    )
    (net (code "117") (name "unconnected-(IC1-PA9-Pad19)") (class "Default")
      (node (ref "IC1") (pin "19") (pinfunction "PA9_19") (pintype "bidirectional"))
    )
    (net (code "118") (name "unconnected-(IC1-PA10-Pad20)") (class "Default")
      (node (ref "IC1") (pin "20") (pinfunction "PA10_20") (pintype "bidirectional"))
    )
    (net (code "119") (name "unconnected-(IC1-PA15-Pad25)") (class "Default")
      (node (ref "IC1") (pin "25") (pinfunction "PA15_25") (pintype "bidirectional"))
    )
    (net (code "120") (name "unconnected-(IC1-PB3-Pad26)") (class "Default")
      (node (ref "IC1") (pin "26") (pinfunction "PB3_26") (pintype "bidirectional"))
    )
    (net (code "121") (name "unconnected-(IC1-PC15-OSC32_OUT-Pad3)") (class "Default")
      (node (ref "IC1") (pin "3") (pinfunction "PC15-OSC32_OUT_3") (pintype "bidirectional"))
    )
    (net (code "122") (name "unconnected-(IC3-~{ALERT}-Pad10)") (class "Default")
      (node (ref "IC3") (pin "10") (pinfunction "~{ALERT}_10") (pintype "open_collector"))
    )
    (net (code "123") (name "unconnected-(IC5-~{FAULT}-Pad6)") (class "Default")
      (node (ref "IC5") (pin "6") (pinfunction "~{FAULT}_6") (pintype "output"))
    )
    (net (code "124") (name "unconnected-(J1-SBU1-PadA8)") (class "Default")
      (node (ref "J1") (pin "A8") (pinfunction "SBU1_A8") (pintype "bidirectional"))
    )
    (net (code "125") (name "unconnected-(J1-SBU2-PadB8)") (class "Default")
      (node (ref "J1") (pin "B8") (pinfunction "SBU2_B8") (pintype "bidirectional"))
    )
    (net (code "126") (name "unconnected-(J2-Pad6)") (class "Default")
      (node (ref "J2") (pin "6") (pinfunction "6_6") (pintype "passive"))
    )
    (net (code "127") (name "unconnected-(J2-Pad7)") (class "Default")
      (node (ref "J2") (pin "7") (pinfunction "7_7") (pintype "passive"))
    )
    (net (code "128") (name "unconnected-(J2-Pad8)") (class "Default")
      (node (ref "J2") (pin "8") (pinfunction "8_8") (pintype "passive"))
    )
    (net (code "129") (name "unconnected-(J2-Pad9)") (class "Default")
      (node (ref "J2") (pin "9") (pinfunction "9_9") (pintype "passive"))
    )
    (net (code "130") (name "unconnected-(SW1-1-PadP1)") (class "Default")
      (node (ref "SW1") (pin "P1") (pinfunction "1_P1") (pintype "passive"))
    )
    (net (code "131") (name "unconnected-(U5-EN-Pad1)") (class "Default")
      (node (ref "U5") (pin "1") (pinfunction "EN_1") (pintype "bidirectional"))
    )
    (net (code "132") (name "unconnected-(X2-CONTACT-Pad3)") (class "Default")
      (node (ref "X2") (pin "3") (pinfunction "CONTACT_3") (pintype "bidirectional"))
    )
    (net (code "133") (name "unconnected-(X3-Pad9)") (class "Default")
      (node (ref "X3") (pin "9") (pinfunction "9_9") (pintype "passive"))
    )
    (net (code "134") (name "~{NRST}") (class "Default")
      (node (ref "IC1") (pin "4") (pinfunction "~{NRST}_4") (pintype "bidirectional"))
      (node (ref "J2") (pin "10") (pinfunction "10_10") (pintype "passive"))
    )
  )
)
